# MusselGapeTracker_RevC.net
KiCad netlist of a schematic drawn in EAGLE
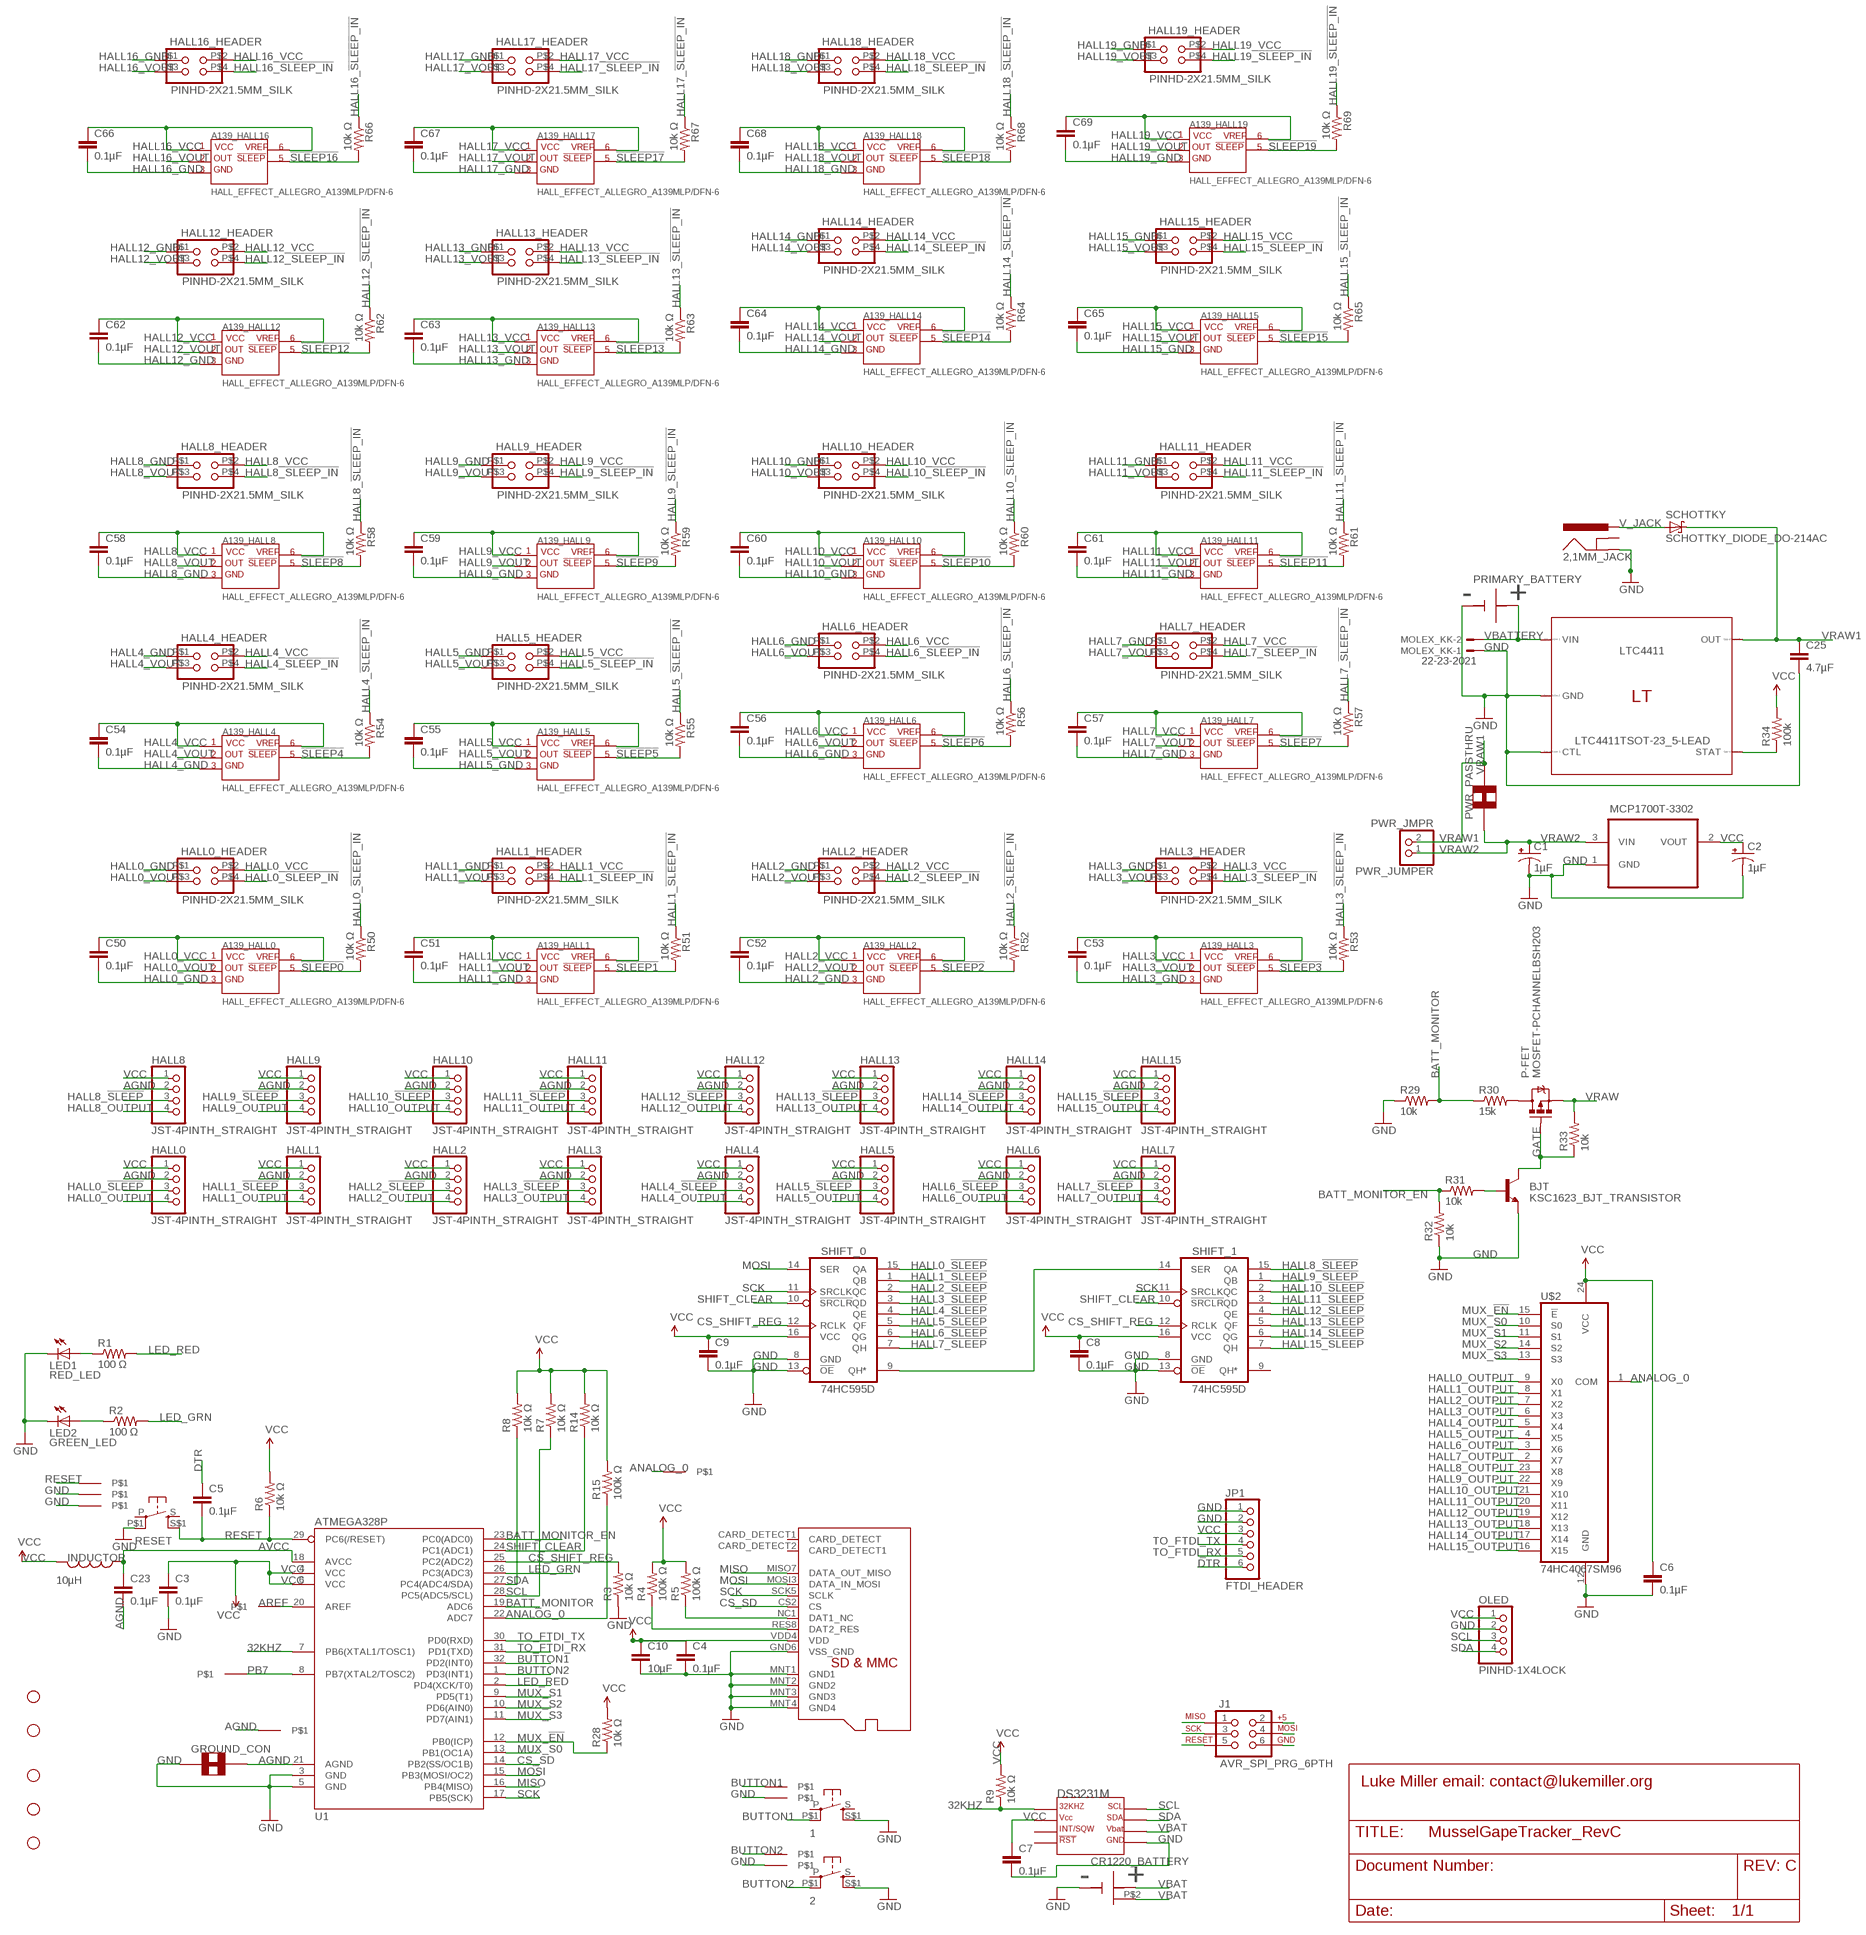
[diagram p0: schematic, sheet 1]

(export (version "E")
  (design (tool "Eeschema 10.0.6"))
  (components
    (comp (ref "1")
      (value "PUSHBUTTON_DPST_SMDSTANDARD")
      (footprint "eagle-import:PUSHBUTTON_DPST_SMD")
      (libsource (lib "eagle-import") (part "PUSHBUTTON_DPST_SMDSTANDARD"))
    )
    (comp (ref "2")
      (value "PUSHBUTTON_DPST_SMDSTANDARD")
      (footprint "eagle-import:PUSHBUTTON_DPST_SMD")
      (libsource (lib "eagle-import") (part "PUSHBUTTON_DPST_SMDSTANDARD"))
    )
    (comp (ref "2,1MM_JACK")
      (value "POWER_JACK_2,1MM")
      (footprint "eagle-import:POWER_JACK_DC_2,1MM")
      (libsource (lib "eagle-import") (part "POWER_JACK_2,1MM"))
    )
    (comp (ref "A139_HALL0")
      (value "HALL_EFFECT_ALLEGRO_A139MLP/DFN-6")
      (footprint "eagle-import:A139__HALL_EFFECT")
      (libsource (lib "eagle-import") (part "HALL_EFFECT_ALLEGRO_A139MLP/DFN-6"))
    )
    (comp (ref "A139_HALL1")
      (value "HALL_EFFECT_ALLEGRO_A139MLP/DFN-6")
      (footprint "eagle-import:A139__HALL_EFFECT")
      (libsource (lib "eagle-import") (part "HALL_EFFECT_ALLEGRO_A139MLP/DFN-6"))
    )
    (comp (ref "A139_HALL2")
      (value "HALL_EFFECT_ALLEGRO_A139MLP/DFN-6")
      (footprint "eagle-import:A139__HALL_EFFECT")
      (libsource (lib "eagle-import") (part "HALL_EFFECT_ALLEGRO_A139MLP/DFN-6"))
    )
    (comp (ref "A139_HALL3")
      (value "HALL_EFFECT_ALLEGRO_A139MLP/DFN-6")
      (footprint "eagle-import:A139__HALL_EFFECT")
      (libsource (lib "eagle-import") (part "HALL_EFFECT_ALLEGRO_A139MLP/DFN-6"))
    )
    (comp (ref "A139_HALL4")
      (value "HALL_EFFECT_ALLEGRO_A139MLP/DFN-6")
      (footprint "eagle-import:A139__HALL_EFFECT")
      (libsource (lib "eagle-import") (part "HALL_EFFECT_ALLEGRO_A139MLP/DFN-6"))
    )
    (comp (ref "A139_HALL5")
      (value "HALL_EFFECT_ALLEGRO_A139MLP/DFN-6")
      (footprint "eagle-import:A139__HALL_EFFECT")
      (libsource (lib "eagle-import") (part "HALL_EFFECT_ALLEGRO_A139MLP/DFN-6"))
    )
    (comp (ref "A139_HALL6")
      (value "HALL_EFFECT_ALLEGRO_A139MLP/DFN-6")
      (footprint "eagle-import:A139__HALL_EFFECT")
      (libsource (lib "eagle-import") (part "HALL_EFFECT_ALLEGRO_A139MLP/DFN-6"))
    )
    (comp (ref "A139_HALL7")
      (value "HALL_EFFECT_ALLEGRO_A139MLP/DFN-6")
      (footprint "eagle-import:A139__HALL_EFFECT")
      (libsource (lib "eagle-import") (part "HALL_EFFECT_ALLEGRO_A139MLP/DFN-6"))
    )
    (comp (ref "A139_HALL8")
      (value "HALL_EFFECT_ALLEGRO_A139MLP/DFN-6")
      (footprint "eagle-import:A139__HALL_EFFECT")
      (libsource (lib "eagle-import") (part "HALL_EFFECT_ALLEGRO_A139MLP/DFN-6"))
    )
    (comp (ref "A139_HALL9")
      (value "HALL_EFFECT_ALLEGRO_A139MLP/DFN-6")
      (footprint "eagle-import:A139__HALL_EFFECT")
      (libsource (lib "eagle-import") (part "HALL_EFFECT_ALLEGRO_A139MLP/DFN-6"))
    )
    (comp (ref "A139_HALL10")
      (value "HALL_EFFECT_ALLEGRO_A139MLP/DFN-6")
      (footprint "eagle-import:A139__HALL_EFFECT")
      (libsource (lib "eagle-import") (part "HALL_EFFECT_ALLEGRO_A139MLP/DFN-6"))
    )
    (comp (ref "A139_HALL11")
      (value "HALL_EFFECT_ALLEGRO_A139MLP/DFN-6")
      (footprint "eagle-import:A139__HALL_EFFECT")
      (libsource (lib "eagle-import") (part "HALL_EFFECT_ALLEGRO_A139MLP/DFN-6"))
    )
    (comp (ref "A139_HALL12")
      (value "HALL_EFFECT_ALLEGRO_A139MLP/DFN-6")
      (footprint "eagle-import:A139__HALL_EFFECT")
      (libsource (lib "eagle-import") (part "HALL_EFFECT_ALLEGRO_A139MLP/DFN-6"))
    )
    (comp (ref "A139_HALL13")
      (value "HALL_EFFECT_ALLEGRO_A139MLP/DFN-6")
      (footprint "eagle-import:A139__HALL_EFFECT")
      (libsource (lib "eagle-import") (part "HALL_EFFECT_ALLEGRO_A139MLP/DFN-6"))
    )
    (comp (ref "A139_HALL14")
      (value "HALL_EFFECT_ALLEGRO_A139MLP/DFN-6")
      (footprint "eagle-import:A139__HALL_EFFECT")
      (libsource (lib "eagle-import") (part "HALL_EFFECT_ALLEGRO_A139MLP/DFN-6"))
    )
    (comp (ref "A139_HALL15")
      (value "HALL_EFFECT_ALLEGRO_A139MLP/DFN-6")
      (footprint "eagle-import:A139__HALL_EFFECT")
      (libsource (lib "eagle-import") (part "HALL_EFFECT_ALLEGRO_A139MLP/DFN-6"))
    )
    (comp (ref "A139_HALL16")
      (value "HALL_EFFECT_ALLEGRO_A139MLP/DFN-6")
      (footprint "eagle-import:A139__HALL_EFFECT")
      (libsource (lib "eagle-import") (part "HALL_EFFECT_ALLEGRO_A139MLP/DFN-6"))
    )
    (comp (ref "A139_HALL17")
      (value "HALL_EFFECT_ALLEGRO_A139MLP/DFN-6")
      (footprint "eagle-import:A139__HALL_EFFECT")
      (libsource (lib "eagle-import") (part "HALL_EFFECT_ALLEGRO_A139MLP/DFN-6"))
    )
    (comp (ref "A139_HALL18")
      (value "HALL_EFFECT_ALLEGRO_A139MLP/DFN-6")
      (footprint "eagle-import:A139__HALL_EFFECT")
      (libsource (lib "eagle-import") (part "HALL_EFFECT_ALLEGRO_A139MLP/DFN-6"))
    )
    (comp (ref "A139_HALL19")
      (value "HALL_EFFECT_ALLEGRO_A139MLP/DFN-6")
      (footprint "eagle-import:A139__HALL_EFFECT")
      (libsource (lib "eagle-import") (part "HALL_EFFECT_ALLEGRO_A139MLP/DFN-6"))
    )
    (comp (ref "BJT")
      (value "KSC1623_BJT_TRANSISTOR")
      (footprint "eagle-import:SOT23")
      (libsource (lib "eagle-import") (part "KSC1623_BJT_TRANSISTOR"))
    )
    (comp (ref "C1")
      (value "1µF")
      (footprint "eagle-import:PANASONIC_B")
      (libsource (lib "eagle-import") (part "CPOL-USB"))
    )
    (comp (ref "C2")
      (value "1µF")
      (footprint "eagle-import:PANASONIC_B")
      (libsource (lib "eagle-import") (part "CPOL-USB"))
    )
    (comp (ref "C3")
      (value "0.1µF")
      (footprint "eagle-import:0603")
      (libsource (lib "eagle-import") (part "CAP0603"))
    )
    (comp (ref "C4")
      (value "0.1µF")
      (footprint "eagle-import:0603")
      (libsource (lib "eagle-import") (part "CAP0603"))
    )
    (comp (ref "C5")
      (value "0.1µF")
      (footprint "eagle-import:0603")
      (libsource (lib "eagle-import") (part "CAP0603"))
    )
    (comp (ref "C6")
      (value "0.1µF")
      (footprint "eagle-import:0603")
      (libsource (lib "eagle-import") (part "CAP0603"))
    )
    (comp (ref "C7")
      (value "0.1µF")
      (footprint "eagle-import:0603")
      (libsource (lib "eagle-import") (part "CAP0603"))
    )
    (comp (ref "C8")
      (value "0.1µF")
      (footprint "eagle-import:0603")
      (libsource (lib "eagle-import") (part "CAP0603"))
    )
    (comp (ref "C9")
      (value "0.1µF")
      (footprint "eagle-import:0603")
      (libsource (lib "eagle-import") (part "CAP0603"))
    )
    (comp (ref "C10")
      (value "10µF")
      (footprint "eagle-import:0603")
      (libsource (lib "eagle-import") (part "CAP0603"))
    )
    (comp (ref "C23")
      (value "0.1µF")
      (footprint "eagle-import:0603")
      (libsource (lib "eagle-import") (part "CAP0603"))
    )
    (comp (ref "C25")
      (value "4.7µF")
      (footprint "eagle-import:0603")
      (libsource (lib "eagle-import") (part "CAP0603"))
    )
    (comp (ref "C50")
      (value "0.1µF")
      (footprint "eagle-import:0603")
      (libsource (lib "eagle-import") (part "CAP0603"))
    )
    (comp (ref "C51")
      (value "0.1µF")
      (footprint "eagle-import:0603")
      (libsource (lib "eagle-import") (part "CAP0603"))
    )
    (comp (ref "C52")
      (value "0.1µF")
      (footprint "eagle-import:0603")
      (libsource (lib "eagle-import") (part "CAP0603"))
    )
    (comp (ref "C53")
      (value "0.1µF")
      (footprint "eagle-import:0603")
      (libsource (lib "eagle-import") (part "CAP0603"))
    )
    (comp (ref "C54")
      (value "0.1µF")
      (footprint "eagle-import:0603")
      (libsource (lib "eagle-import") (part "CAP0603"))
    )
    (comp (ref "C55")
      (value "0.1µF")
      (footprint "eagle-import:0603")
      (libsource (lib "eagle-import") (part "CAP0603"))
    )
    (comp (ref "C56")
      (value "0.1µF")
      (footprint "eagle-import:0603")
      (libsource (lib "eagle-import") (part "CAP0603"))
    )
    (comp (ref "C57")
      (value "0.1µF")
      (footprint "eagle-import:0603")
      (libsource (lib "eagle-import") (part "CAP0603"))
    )
    (comp (ref "C58")
      (value "0.1µF")
      (footprint "eagle-import:0603")
      (libsource (lib "eagle-import") (part "CAP0603"))
    )
    (comp (ref "C59")
      (value "0.1µF")
      (footprint "eagle-import:0603")
      (libsource (lib "eagle-import") (part "CAP0603"))
    )
    (comp (ref "C60")
      (value "0.1µF")
      (footprint "eagle-import:0603")
      (libsource (lib "eagle-import") (part "CAP0603"))
    )
    (comp (ref "C61")
      (value "0.1µF")
      (footprint "eagle-import:0603")
      (libsource (lib "eagle-import") (part "CAP0603"))
    )
    (comp (ref "C62")
      (value "0.1µF")
      (footprint "eagle-import:0603")
      (libsource (lib "eagle-import") (part "CAP0603"))
    )
    (comp (ref "C63")
      (value "0.1µF")
      (footprint "eagle-import:0603")
      (libsource (lib "eagle-import") (part "CAP0603"))
    )
    (comp (ref "C64")
      (value "0.1µF")
      (footprint "eagle-import:0603")
      (libsource (lib "eagle-import") (part "CAP0603"))
    )
    (comp (ref "C65")
      (value "0.1µF")
      (footprint "eagle-import:0603")
      (libsource (lib "eagle-import") (part "CAP0603"))
    )
    (comp (ref "C66")
      (value "0.1µF")
      (footprint "eagle-import:0603")
      (libsource (lib "eagle-import") (part "CAP0603"))
    )
    (comp (ref "C67")
      (value "0.1µF")
      (footprint "eagle-import:0603")
      (libsource (lib "eagle-import") (part "CAP0603"))
    )
    (comp (ref "C68")
      (value "0.1µF")
      (footprint "eagle-import:0603")
      (libsource (lib "eagle-import") (part "CAP0603"))
    )
    (comp (ref "C69")
      (value "0.1µF")
      (footprint "eagle-import:0603")
      (libsource (lib "eagle-import") (part "CAP0603"))
    )
    (comp (ref "CR1220_BATTERY")
      (value "CR1220_BATTERY_HOLDERSMD")
      (footprint "eagle-import:CR1220_BATTERY_HOLDER_SMD")
      (libsource (lib "eagle-import") (part "CR1220_BATTERY_HOLDERSMD"))
    )
    (comp (ref "DS3231M")
      (value "DS3231MSOIC-8")
      (footprint "eagle-import:DS3231M_SOIC8")
      (libsource (lib "eagle-import") (part "DS3231MSOIC-8"))
    )
    (comp (ref "GND")
      (value "PINHD-1X1SMALL")
      (footprint "eagle-import:1X01_SMALL")
      (libsource (lib "eagle-import") (part "PINHD-1X1SMALL"))
    )
    (comp (ref "GROUND_CON")
      (value "SOLDER_JUMPER_TRACESTANDARD")
      (footprint "eagle-import:SJ_2S-TRACE")
      (libsource (lib "eagle-import") (part "SOLDER_JUMPER_TRACESTANDARD"))
    )
    (comp (ref "HALL0")
      (value "JST-4PINTH_STRAIGHT")
      (footprint "eagle-import:JST-PH-4-THM")
      (libsource (lib "eagle-import") (part "JST-4PINTH_STRAIGHT"))
    )
    (comp (ref "HALL0_HEADER")
      (value "PINHD-2X21.5MM_SILK")
      (footprint "eagle-import:2X2_1.5MM")
      (libsource (lib "eagle-import") (part "PINHD-2X21.5MM_SILK"))
    )
    (comp (ref "HALL1")
      (value "JST-4PINTH_STRAIGHT")
      (footprint "eagle-import:JST-PH-4-THM")
      (libsource (lib "eagle-import") (part "JST-4PINTH_STRAIGHT"))
    )
    (comp (ref "HALL1_HEADER")
      (value "PINHD-2X21.5MM_SILK")
      (footprint "eagle-import:2X2_1.5MM")
      (libsource (lib "eagle-import") (part "PINHD-2X21.5MM_SILK"))
    )
    (comp (ref "HALL2")
      (value "JST-4PINTH_STRAIGHT")
      (footprint "eagle-import:JST-PH-4-THM")
      (libsource (lib "eagle-import") (part "JST-4PINTH_STRAIGHT"))
    )
    (comp (ref "HALL2_HEADER")
      (value "PINHD-2X21.5MM_SILK")
      (footprint "eagle-import:2X2_1.5MM")
      (libsource (lib "eagle-import") (part "PINHD-2X21.5MM_SILK"))
    )
    (comp (ref "HALL3")
      (value "JST-4PINTH_STRAIGHT")
      (footprint "eagle-import:JST-PH-4-THM")
      (libsource (lib "eagle-import") (part "JST-4PINTH_STRAIGHT"))
    )
    (comp (ref "HALL3_HEADER")
      (value "PINHD-2X21.5MM_SILK")
      (footprint "eagle-import:2X2_1.5MM")
      (libsource (lib "eagle-import") (part "PINHD-2X21.5MM_SILK"))
    )
    (comp (ref "HALL4")
      (value "JST-4PINTH_STRAIGHT")
      (footprint "eagle-import:JST-PH-4-THM")
      (libsource (lib "eagle-import") (part "JST-4PINTH_STRAIGHT"))
    )
    (comp (ref "HALL4_HEADER")
      (value "PINHD-2X21.5MM_SILK")
      (footprint "eagle-import:2X2_1.5MM")
      (libsource (lib "eagle-import") (part "PINHD-2X21.5MM_SILK"))
    )
    (comp (ref "HALL5")
      (value "JST-4PINTH_STRAIGHT")
      (footprint "eagle-import:JST-PH-4-THM")
      (libsource (lib "eagle-import") (part "JST-4PINTH_STRAIGHT"))
    )
    (comp (ref "HALL5_HEADER")
      (value "PINHD-2X21.5MM_SILK")
      (footprint "eagle-import:2X2_1.5MM")
      (libsource (lib "eagle-import") (part "PINHD-2X21.5MM_SILK"))
    )
    (comp (ref "HALL6")
      (value "JST-4PINTH_STRAIGHT")
      (footprint "eagle-import:JST-PH-4-THM")
      (libsource (lib "eagle-import") (part "JST-4PINTH_STRAIGHT"))
    )
    (comp (ref "HALL6_HEADER")
      (value "PINHD-2X21.5MM_SILK")
      (footprint "eagle-import:2X2_1.5MM")
      (libsource (lib "eagle-import") (part "PINHD-2X21.5MM_SILK"))
    )
    (comp (ref "HALL7")
      (value "JST-4PINTH_STRAIGHT")
      (footprint "eagle-import:JST-PH-4-THM")
      (libsource (lib "eagle-import") (part "JST-4PINTH_STRAIGHT"))
    )
    (comp (ref "HALL7_HEADER")
      (value "PINHD-2X21.5MM_SILK")
      (footprint "eagle-import:2X2_1.5MM")
      (libsource (lib "eagle-import") (part "PINHD-2X21.5MM_SILK"))
    )
    (comp (ref "HALL8")
      (value "JST-4PINTH_STRAIGHT")
      (footprint "eagle-import:JST-PH-4-THM")
      (libsource (lib "eagle-import") (part "JST-4PINTH_STRAIGHT"))
    )
    (comp (ref "HALL8_HEADER")
      (value "PINHD-2X21.5MM_SILK")
      (footprint "eagle-import:2X2_1.5MM")
      (libsource (lib "eagle-import") (part "PINHD-2X21.5MM_SILK"))
    )
    (comp (ref "HALL9")
      (value "JST-4PINTH_STRAIGHT")
      (footprint "eagle-import:JST-PH-4-THM")
      (libsource (lib "eagle-import") (part "JST-4PINTH_STRAIGHT"))
    )
    (comp (ref "HALL9_HEADER")
      (value "PINHD-2X21.5MM_SILK")
      (footprint "eagle-import:2X2_1.5MM")
      (libsource (lib "eagle-import") (part "PINHD-2X21.5MM_SILK"))
    )
    (comp (ref "HALL10")
      (value "JST-4PINTH_STRAIGHT")
      (footprint "eagle-import:JST-PH-4-THM")
      (libsource (lib "eagle-import") (part "JST-4PINTH_STRAIGHT"))
    )
    (comp (ref "HALL10_HEADER")
      (value "PINHD-2X21.5MM_SILK")
      (footprint "eagle-import:2X2_1.5MM")
      (libsource (lib "eagle-import") (part "PINHD-2X21.5MM_SILK"))
    )
    (comp (ref "HALL11")
      (value "JST-4PINTH_STRAIGHT")
      (footprint "eagle-import:JST-PH-4-THM")
      (libsource (lib "eagle-import") (part "JST-4PINTH_STRAIGHT"))
    )
    (comp (ref "HALL11_HEADER")
      (value "PINHD-2X21.5MM_SILK")
      (footprint "eagle-import:2X2_1.5MM")
      (libsource (lib "eagle-import") (part "PINHD-2X21.5MM_SILK"))
    )
    (comp (ref "HALL12")
      (value "JST-4PINTH_STRAIGHT")
      (footprint "eagle-import:JST-PH-4-THM")
      (libsource (lib "eagle-import") (part "JST-4PINTH_STRAIGHT"))
    )
    (comp (ref "HALL12_HEADER")
      (value "PINHD-2X21.5MM_SILK")
      (footprint "eagle-import:2X2_1.5MM")
      (libsource (lib "eagle-import") (part "PINHD-2X21.5MM_SILK"))
    )
    (comp (ref "HALL13")
      (value "JST-4PINTH_STRAIGHT")
      (footprint "eagle-import:JST-PH-4-THM")
      (libsource (lib "eagle-import") (part "JST-4PINTH_STRAIGHT"))
    )
    (comp (ref "HALL13_HEADER")
      (value "PINHD-2X21.5MM_SILK")
      (footprint "eagle-import:2X2_1.5MM")
      (libsource (lib "eagle-import") (part "PINHD-2X21.5MM_SILK"))
    )
    (comp (ref "HALL14")
      (value "JST-4PINTH_STRAIGHT")
      (footprint "eagle-import:JST-PH-4-THM")
      (libsource (lib "eagle-import") (part "JST-4PINTH_STRAIGHT"))
    )
    (comp (ref "HALL14_HEADER")
      (value "PINHD-2X21.5MM_SILK")
      (footprint "eagle-import:2X2_1.5MM")
      (libsource (lib "eagle-import") (part "PINHD-2X21.5MM_SILK"))
    )
    (comp (ref "HALL15")
      (value "JST-4PINTH_STRAIGHT")
      (footprint "eagle-import:JST-PH-4-THM")
      (libsource (lib "eagle-import") (part "JST-4PINTH_STRAIGHT"))
    )
    (comp (ref "HALL15_HEADER")
      (value "PINHD-2X21.5MM_SILK")
      (footprint "eagle-import:2X2_1.5MM")
      (libsource (lib "eagle-import") (part "PINHD-2X21.5MM_SILK"))
    )
    (comp (ref "HALL16_HEADER")
      (value "PINHD-2X21.5MM_SILK")
      (footprint "eagle-import:2X2_1.5MM")
      (libsource (lib "eagle-import") (part "PINHD-2X21.5MM_SILK"))
    )
    (comp (ref "HALL17_HEADER")
      (value "PINHD-2X21.5MM_SILK")
      (footprint "eagle-import:2X2_1.5MM")
      (libsource (lib "eagle-import") (part "PINHD-2X21.5MM_SILK"))
    )
    (comp (ref "HALL18_HEADER")
      (value "PINHD-2X21.5MM_SILK")
      (footprint "eagle-import:2X2_1.5MM")
      (libsource (lib "eagle-import") (part "PINHD-2X21.5MM_SILK"))
    )
    (comp (ref "HALL19_HEADER")
      (value "PINHD-2X21.5MM_SILK")
      (footprint "eagle-import:2X2_1.5MM")
      (libsource (lib "eagle-import") (part "PINHD-2X21.5MM_SILK"))
    )
    (comp (ref "INDUCTOR")
      (value "10µH")
      (footprint "eagle-import:I_0805")
      (libsource (lib "eagle-import") (part "INDUCTOR0805_TY"))
    )
    (comp (ref "J1")
      (value "AVR_SPI_PRG_6PTH")
      (footprint "eagle-import:2X3")
      (libsource (lib "eagle-import") (part "AVR_SPI_PRG_6PTH"))
    )
    (comp (ref "JP1")
      (value "FTDI_HEADER")
      (footprint "eagle-import:1X06-RIGHT_ANGLE")
      (libsource (lib "eagle-import") (part "PINHD-1X6RA"))
    )
    (comp (ref "LED1")
      (value "RED_LED")
      (footprint "eagle-import:CHIPLED_0805")
      (libsource (lib "eagle-import") (part "LED0805"))
    )
    (comp (ref "LED2")
      (value "GREEN_LED")
      (footprint "eagle-import:CHIPLED_0805")
      (libsource (lib "eagle-import") (part "LED0805"))
    )
    (comp (ref "LTC4411")
      (value "LTC4411TSOT-23_5-LEAD")
      (footprint "eagle-import:TSOT-23_5-LEAD")
      (libsource (lib "eagle-import") (part "LTC4411TSOT-23_5-LEAD"))
    )
    (comp (ref "MCP1700T-3302")
      (value "MCP1700T-3302E/TT")
      (footprint "eagle-import:SOT95P237X112-3N")
      (libsource (lib "eagle-import") (part "MCP1700T-3302E/TT"))
    )
    (comp (ref "MOLEX_KK")
      (value "22-23-2021")
      (footprint "eagle-import:22-23-2021")
      (fields (field (name "MF") "MOLEX"))
      (libsource (lib "eagle-import") (part "22-23-2021"))
    )
    (comp (ref "OLED")
      (value "PINHD-1X4LOCK")
      (footprint "eagle-import:1X04_LOCK")
      (libsource (lib "eagle-import") (part "PINHD-1X4LOCK"))
    )
    (comp (ref "P-FET")
      (value "MOSFET-PCHANNELBSH203")
      (footprint "eagle-import:SOT23-3")
      (libsource (lib "eagle-import") (part "MOSFET-PCHANNELBSH203"))
    )
    (comp (ref "PB7")
      (value "PINHD-1X1SMALL")
      (footprint "eagle-import:1X01_SMALL")
      (libsource (lib "eagle-import") (part "PINHD-1X1SMALL"))
    )
    (comp (ref "PRIMARY_BATTERY")
      (value "BATTERY_4XAA")
      (footprint "eagle-import:BATTERY_4XAA_PTH")
      (libsource (lib "eagle-import") (part "BATTERY_4XAA"))
    )
    (comp (ref "PWR_JUMPER")
      (value "PWR_JMPR")
      (footprint "eagle-import:1X02_NOSILK")
      (libsource (lib "eagle-import") (part "PINHD-1X2NOSILK"))
    )
    (comp (ref "PWR_PASSTHRU")
      (value "PWR")
      (footprint "eagle-import:SJ_2S-TRACE")
      (libsource (lib "eagle-import") (part "SOLDER_JUMPER_TRACESTANDARD"))
    )
    (comp (ref "R1")
      (value "100 Ω")
      (footprint "eagle-import:R0603")
      (libsource (lib "eagle-import") (part "RESISTOR_SMDR0603"))
    )
    (comp (ref "R2")
      (value "100 Ω")
      (footprint "eagle-import:R0603")
      (libsource (lib "eagle-import") (part "RESISTOR_SMDR0603"))
    )
    (comp (ref "R3")
      (value "10k Ω")
      (footprint "eagle-import:R0603")
      (libsource (lib "eagle-import") (part "RESISTOR_SMDR0603"))
    )
    (comp (ref "R4")
      (value "100k Ω")
      (footprint "eagle-import:R0603")
      (libsource (lib "eagle-import") (part "RESISTOR_SMDR0603"))
    )
    (comp (ref "R5")
      (value "100k Ω")
      (footprint "eagle-import:R0603")
      (libsource (lib "eagle-import") (part "RESISTOR_SMDR0603"))
    )
    (comp (ref "R6")
      (value "10k Ω")
      (footprint "eagle-import:R0603")
      (libsource (lib "eagle-import") (part "RESISTOR_SMDR0603"))
    )
    (comp (ref "R7")
      (value "10k Ω")
      (footprint "eagle-import:R0603")
      (libsource (lib "eagle-import") (part "RESISTOR_SMDR0603"))
    )
    (comp (ref "R8")
      (value "10k Ω")
      (footprint "eagle-import:R0603")
      (libsource (lib "eagle-import") (part "RESISTOR_SMDR0603"))
    )
    (comp (ref "R9")
      (value "10k Ω")
      (footprint "eagle-import:R0603")
      (libsource (lib "eagle-import") (part "RESISTOR_SMDR0603"))
    )
    (comp (ref "R14")
      (value "10k Ω")
      (footprint "eagle-import:R0603")
      (libsource (lib "eagle-import") (part "RESISTOR_SMDR0603"))
    )
    (comp (ref "R15")
      (value "100k Ω")
      (footprint "eagle-import:R0603")
      (libsource (lib "eagle-import") (part "RESISTOR_SMDR0603"))
    )
    (comp (ref "R28")
      (value "10k Ω")
      (footprint "eagle-import:R0603")
      (libsource (lib "eagle-import") (part "RESISTOR_SMDR0603"))
    )
    (comp (ref "R29")
      (value "10k")
      (footprint "eagle-import:R0603")
      (libsource (lib "eagle-import") (part "RESISTOR_SMDR0603"))
    )
    (comp (ref "R30")
      (value "15k")
      (footprint "eagle-import:R0603")
      (libsource (lib "eagle-import") (part "RESISTOR_SMDR0603"))
    )
    (comp (ref "R31")
      (value "10k")
      (footprint "eagle-import:R0603")
      (libsource (lib "eagle-import") (part "RESISTOR_SMDR0603"))
    )
    (comp (ref "R32")
      (value "10k")
      (footprint "eagle-import:R0603")
      (libsource (lib "eagle-import") (part "RESISTOR_SMDR0603"))
    )
    (comp (ref "R33")
      (value "10k")
      (footprint "eagle-import:R0603")
      (libsource (lib "eagle-import") (part "RESISTOR_SMDR0603"))
    )
    (comp (ref "R34")
      (value "100k")
      (footprint "eagle-import:R0603")
      (libsource (lib "eagle-import") (part "RESISTOR_SMDR0603"))
    )
    (comp (ref "R50")
      (value "10k Ω")
      (footprint "eagle-import:R0603")
      (libsource (lib "eagle-import") (part "RESISTOR_SMDR0603"))
    )
    (comp (ref "R51")
      (value "10k Ω")
      (footprint "eagle-import:R0603")
      (libsource (lib "eagle-import") (part "RESISTOR_SMDR0603"))
    )
    (comp (ref "R52")
      (value "10k Ω")
      (footprint "eagle-import:R0603")
      (libsource (lib "eagle-import") (part "RESISTOR_SMDR0603"))
    )
    (comp (ref "R53")
      (value "10k Ω")
      (footprint "eagle-import:R0603")
      (libsource (lib "eagle-import") (part "RESISTOR_SMDR0603"))
    )
    (comp (ref "R54")
      (value "10k Ω")
      (footprint "eagle-import:R0603")
      (libsource (lib "eagle-import") (part "RESISTOR_SMDR0603"))
    )
    (comp (ref "R55")
      (value "10k Ω")
      (footprint "eagle-import:R0603")
      (libsource (lib "eagle-import") (part "RESISTOR_SMDR0603"))
    )
    (comp (ref "R56")
      (value "10k Ω")
      (footprint "eagle-import:R0603")
      (libsource (lib "eagle-import") (part "RESISTOR_SMDR0603"))
    )
    (comp (ref "R57")
      (value "10k Ω")
      (footprint "eagle-import:R0603")
      (libsource (lib "eagle-import") (part "RESISTOR_SMDR0603"))
    )
    (comp (ref "R58")
      (value "10k Ω")
      (footprint "eagle-import:R0603")
      (libsource (lib "eagle-import") (part "RESISTOR_SMDR0603"))
    )
    (comp (ref "R59")
      (value "10k Ω")
      (footprint "eagle-import:R0603")
      (libsource (lib "eagle-import") (part "RESISTOR_SMDR0603"))
    )
    (comp (ref "R60")
      (value "10k Ω")
      (footprint "eagle-import:R0603")
      (libsource (lib "eagle-import") (part "RESISTOR_SMDR0603"))
    )
    (comp (ref "R61")
      (value "10k Ω")
      (footprint "eagle-import:R0603")
      (libsource (lib "eagle-import") (part "RESISTOR_SMDR0603"))
    )
    (comp (ref "R62")
      (value "10k Ω")
      (footprint "eagle-import:R0603")
      (libsource (lib "eagle-import") (part "RESISTOR_SMDR0603"))
    )
    (comp (ref "R63")
      (value "10k Ω")
      (footprint "eagle-import:R0603")
      (libsource (lib "eagle-import") (part "RESISTOR_SMDR0603"))
    )
    (comp (ref "R64")
      (value "10k Ω")
      (footprint "eagle-import:R0603")
      (libsource (lib "eagle-import") (part "RESISTOR_SMDR0603"))
    )
    (comp (ref "R65")
      (value "10k Ω")
      (footprint "eagle-import:R0603")
      (libsource (lib "eagle-import") (part "RESISTOR_SMDR0603"))
    )
    (comp (ref "R66")
      (value "10k Ω")
      (footprint "eagle-import:R0603")
      (libsource (lib "eagle-import") (part "RESISTOR_SMDR0603"))
    )
    (comp (ref "R67")
      (value "10k Ω")
      (footprint "eagle-import:R0603")
      (libsource (lib "eagle-import") (part "RESISTOR_SMDR0603"))
    )
    (comp (ref "R68")
      (value "10k Ω")
      (footprint "eagle-import:R0603")
      (libsource (lib "eagle-import") (part "RESISTOR_SMDR0603"))
    )
    (comp (ref "R69")
      (value "10k Ω")
      (footprint "eagle-import:R0603")
      (libsource (lib "eagle-import") (part "RESISTOR_SMDR0603"))
    )
    (comp (ref "RESET")
      (value "PUSHBUTTON_DPST_SMDSTANDARD")
      (footprint "eagle-import:PUSHBUTTON_DPST_SMD")
      (libsource (lib "eagle-import") (part "PUSHBUTTON_DPST_SMDSTANDARD"))
    )
    (comp (ref "SCHOTTKY")
      (value "SCHOTTKY_DIODE_DO-214AC")
      (footprint "eagle-import:DO214AC")
      (libsource (lib "eagle-import") (part "SCHOTTKY_DIODE_DO-214AC"))
    )
    (comp (ref "SHIFT_0")
      (value "74HC595D")
      (footprint "eagle-import:SO16")
      (libsource (lib "eagle-import") (part "74HC595D"))
    )
    (comp (ref "SHIFT_1")
      (value "74HC595D")
      (footprint "eagle-import:SO16")
      (libsource (lib "eagle-import") (part "74HC595D"))
    )
    (comp (ref "STANDOFF1")
      (value "STAND-OFF4-40")
      (footprint "eagle-import:STAND-OFF")
      (libsource (lib "eagle-import") (part "STAND-OFF4-40"))
    )
    (comp (ref "STANDOFF2")
      (value "STAND-OFF4-40")
      (footprint "eagle-import:STAND-OFF")
      (libsource (lib "eagle-import") (part "STAND-OFF4-40"))
    )
    (comp (ref "STANDOFF3")
      (value "STAND-OFF4-40")
      (footprint "eagle-import:STAND-OFF")
      (libsource (lib "eagle-import") (part "STAND-OFF4-40"))
    )
    (comp (ref "STANDOFF4_M2")
      (value "STAND-OFFM2")
      (footprint "eagle-import:STAND-OFF_M2")
      (libsource (lib "eagle-import") (part "STAND-OFFM2"))
    )
    (comp (ref "STANDOFF5_M2")
      (value "STAND-OFFM2")
      (footprint "eagle-import:STAND-OFF_M2")
      (libsource (lib "eagle-import") (part "STAND-OFFM2"))
    )
    (comp (ref "U$1")
      (value "MICROSD_MOLEX_REVERSECURRENT")
      (footprint "eagle-import:MICROSD_SOCKET_MOLEX_REVERSEMOUNT")
      (libsource (lib "eagle-import") (part "MICROSD_MOLEX_REVERSECURRENT"))
    )
    (comp (ref "U$2")
      (value "74HC4067SM96")
      (footprint "eagle-import:SSOP24")
      (libsource (lib "eagle-import") (part "74HC4067SM96"))
    )
    (comp (ref "U$3")
      (value "PINHD-1X1SMALL")
      (footprint "eagle-import:1X01_SMALL")
      (libsource (lib "eagle-import") (part "PINHD-1X1SMALL"))
    )
    (comp (ref "U$4")
      (value "PINHD-1X1SMALL")
      (footprint "eagle-import:1X01_SMALL")
      (libsource (lib "eagle-import") (part "PINHD-1X1SMALL"))
    )
    (comp (ref "U$6")
      (value "PINHD-1X1SMALL")
      (footprint "eagle-import:1X01_SMALL")
      (libsource (lib "eagle-import") (part "PINHD-1X1SMALL"))
    )
    (comp (ref "U$7")
      (value "PINHD-1X1SMALL")
      (footprint "eagle-import:1X01_SMALL")
      (libsource (lib "eagle-import") (part "PINHD-1X1SMALL"))
    )
    (comp (ref "U$8")
      (value "PINHD-1X1SMALL")
      (footprint "eagle-import:1X01_SMALL")
      (libsource (lib "eagle-import") (part "PINHD-1X1SMALL"))
    )
    (comp (ref "U$9")
      (value "PINHD-1X1SMALL")
      (footprint "eagle-import:1X01_SMALL")
      (libsource (lib "eagle-import") (part "PINHD-1X1SMALL"))
    )
    (comp (ref "U$10")
      (value "PINHD-1X1SMALL")
      (footprint "eagle-import:1X01_SMALL")
      (libsource (lib "eagle-import") (part "PINHD-1X1SMALL"))
    )
    (comp (ref "U$11")
      (value "PINHD-1X1SMALL")
      (footprint "eagle-import:1X01_SMALL")
      (libsource (lib "eagle-import") (part "PINHD-1X1SMALL"))
    )
    (comp (ref "U$17")
      (value "PINHD-1X1SMALL")
      (footprint "eagle-import:1X01_SMALL")
      (libsource (lib "eagle-import") (part "PINHD-1X1SMALL"))
    )
    (comp (ref "U1")
      (value "ATMEGA328P")
      (footprint "eagle-import:TQFP32-08")
      (libsource (lib "eagle-import") (part "ATMEGA328_SMT"))
    )
  )
  (nets
    (net (code "1") (name "/32KHZ") (class "Default")
      (node (ref "DS3231M") (pin "1") (pinfunction "P$1_32KHZ_1") (pintype "bidirectional"))
      (node (ref "R9") (pin "1") (pinfunction "1_1") (pintype "passive"))
      (node (ref "U1") (pin "7") (pinfunction "PB6(XTAL1/TOSC1)_7") (pintype "bidirectional"))
    )
    (net (code "2") (name "/AGND") (class "Default")
      (node (ref "C23") (pin "2") (pinfunction "2_2") (pintype "passive"))
      (node (ref "GROUND_CON") (pin "2") (pinfunction "P$2_2") (pintype "bidirectional"))
      (node (ref "HALL0") (pin "2") (pinfunction "2_2") (pintype "passive"))
      (node (ref "HALL1") (pin "2") (pinfunction "2_2") (pintype "passive"))
      (node (ref "HALL10") (pin "2") (pinfunction "2_2") (pintype "passive"))
      (node (ref "HALL11") (pin "2") (pinfunction "2_2") (pintype "passive"))
      (node (ref "HALL12") (pin "2") (pinfunction "2_2") (pintype "passive"))
      (node (ref "HALL13") (pin "2") (pinfunction "2_2") (pintype "passive"))
      (node (ref "HALL14") (pin "2") (pinfunction "2_2") (pintype "passive"))
      (node (ref "HALL15") (pin "2") (pinfunction "2_2") (pintype "passive"))
      (node (ref "HALL2") (pin "2") (pinfunction "2_2") (pintype "passive"))
      (node (ref "HALL3") (pin "2") (pinfunction "2_2") (pintype "passive"))
      (node (ref "HALL4") (pin "2") (pinfunction "2_2") (pintype "passive"))
      (node (ref "HALL5") (pin "2") (pinfunction "2_2") (pintype "passive"))
      (node (ref "HALL6") (pin "2") (pinfunction "2_2") (pintype "passive"))
      (node (ref "HALL7") (pin "2") (pinfunction "2_2") (pintype "passive"))
      (node (ref "HALL8") (pin "2") (pinfunction "2_2") (pintype "passive"))
      (node (ref "HALL9") (pin "2") (pinfunction "2_2") (pintype "passive"))
      (node (ref "U$11") (pin "1") (pinfunction "P$1_1") (pintype "bidirectional"))
      (node (ref "U1") (pin "21") (pinfunction "AGND_21") (pintype "bidirectional"))
    )
    (net (code "3") (name "/ANALOG_0") (class "Default")
      (node (ref "R15") (pin "1") (pinfunction "1_1") (pintype "passive"))
      (node (ref "U$10") (pin "1") (pinfunction "P$1_1") (pintype "bidirectional"))
      (node (ref "U$2") (pin "1") (pinfunction "COM_1") (pintype "output"))
      (node (ref "U1") (pin "22") (pinfunction "ADC7_22") (pintype "bidirectional"))
    )
    (net (code "4") (name "/AREF") (class "Default")
      (node (ref "U$17") (pin "1") (pinfunction "P$1_1") (pintype "bidirectional"))
      (node (ref "U1") (pin "20") (pinfunction "AREF_20") (pintype "bidirectional"))
    )
    (net (code "5") (name "/AVCC") (class "Default")
      (node (ref "C23") (pin "1") (pinfunction "1_1") (pintype "passive"))
      (node (ref "INDUCTOR") (pin "P$1") (pinfunction "1_P$1") (pintype "passive"))
      (node (ref "U1") (pin "18") (pinfunction "AVCC_18") (pintype "bidirectional"))
    )
    (net (code "6") (name "/BATT_MONITOR") (class "Default")
      (node (ref "R29") (pin "2") (pinfunction "2_2") (pintype "passive"))
      (node (ref "R30") (pin "1") (pinfunction "1_1") (pintype "passive"))
      (node (ref "U1") (pin "19") (pinfunction "ADC6_19") (pintype "bidirectional"))
    )
    (net (code "7") (name "/BATT_MONITOR_EN") (class "Default")
      (node (ref "R31") (pin "1") (pinfunction "1_1") (pintype "passive"))
      (node (ref "R32") (pin "2") (pinfunction "2_2") (pintype "passive"))
      (node (ref "U1") (pin "23") (pinfunction "PC0(ADC0)_23") (pintype "bidirectional"))
    )
    (net (code "8") (name "/BUTTON1") (class "Default")
      (node (ref "1") (pin "P$1") (pinfunction "P1_P$1") (pintype "passive"))
      (node (ref "U$6") (pin "1") (pinfunction "P$1_1") (pintype "bidirectional"))
      (node (ref "U1") (pin "32") (pinfunction "PD2(INT0)_32") (pintype "bidirectional"))
    )
    (net (code "9") (name "/BUTTON2") (class "Default")
      (node (ref "2") (pin "P$1") (pinfunction "P1_P$1") (pintype "passive"))
      (node (ref "U$8") (pin "1") (pinfunction "P$1_1") (pintype "bidirectional"))
      (node (ref "U1") (pin "1") (pinfunction "PD3(INT1)_1") (pintype "bidirectional"))
    )
    (net (code "10") (name "/CS_SD") (class "Default")
      (node (ref "U$1") (pin "CS2") (pinfunction "CS_CS2") (pintype "input"))
      (node (ref "U1") (pin "14") (pinfunction "PB2(SS/OC1B)_14") (pintype "bidirectional"))
    )
    (net (code "11") (name "/CS_SHIFT_REG") (class "Default")
      (node (ref "R3") (pin "2") (pinfunction "2_2") (pintype "passive"))
      (node (ref "SHIFT_0") (pin "12") (pinfunction "RCLK_12") (pintype "input"))
      (node (ref "SHIFT_1") (pin "12") (pinfunction "RCLK_12") (pintype "input"))
      (node (ref "U1") (pin "25") (pinfunction "PC2(ADC2)_25") (pintype "bidirectional"))
    )
    (net (code "12") (name "/DTR") (class "Default")
      (node (ref "C5") (pin "1") (pinfunction "1_1") (pintype "passive"))
      (node (ref "JP1") (pin "6") (pinfunction "6_6") (pintype "passive"))
    )
    (net (code "13") (name "/GATE") (class "Default")
      (node (ref "BJT") (pin "3") (pinfunction "C_3") (pintype "passive"))
      (node (ref "P-FET") (pin "1") (pinfunction "G_1") (pintype "passive"))
      (node (ref "R33") (pin "1") (pinfunction "1_1") (pintype "passive"))
    )
    (net (code "14") (name "/HALL0_GND") (class "Default")
      (node (ref "A139_HALL0") (pin "P$3_4") (pinfunction "P$3_P$3_4") (pintype "bidirectional"))
      (node (ref "C50") (pin "2") (pinfunction "2_2") (pintype "passive"))
      (node (ref "HALL0_HEADER") (pin "P$1") (pinfunction "1_P$1") (pintype "passive"))
    )
    (net (code "15") (name "/HALL0_OUTPUT") (class "Default")
      (node (ref "HALL0") (pin "4") (pinfunction "4_4") (pintype "passive"))
      (node (ref "U$2") (pin "9") (pinfunction "X0_9") (pintype "input"))
    )
    (net (code "16") (name "/HALL0_VCC") (class "Default")
      (node (ref "A139_HALL0") (pin "P$1") (pinfunction "P$1_P$1") (pintype "bidirectional"))
      (node (ref "A139_HALL0") (pin "P$6") (pinfunction "P$6_P$6") (pintype "bidirectional"))
      (node (ref "C50") (pin "1") (pinfunction "1_1") (pintype "passive"))
      (node (ref "HALL0_HEADER") (pin "P$2") (pinfunction "2_P$2") (pintype "passive"))
    )
    (net (code "17") (name "/HALL0_VOUT") (class "Default")
      (node (ref "A139_HALL0") (pin "P$2") (pinfunction "P$2_P$2") (pintype "bidirectional"))
      (node (ref "HALL0_HEADER") (pin "P$3") (pinfunction "3_P$3") (pintype "passive"))
    )
    (net (code "18") (name "/HALL0_~{SLEEP_IN}") (class "Default")
      (node (ref "HALL0_HEADER") (pin "P$4") (pinfunction "4_P$4") (pintype "passive"))
      (node (ref "R50") (pin "1") (pinfunction "1_1") (pintype "passive"))
    )
    (net (code "19") (name "/HALL0_~{SLEEP}") (class "Default")
      (node (ref "HALL0") (pin "3") (pinfunction "3_3") (pintype "passive"))
      (node (ref "SHIFT_0") (pin "15") (pinfunction "QA_15") (pintype "tri_state"))
    )
    (net (code "20") (name "/HALL1_GND") (class "Default")
      (node (ref "A139_HALL1") (pin "P$3_4") (pinfunction "P$3_P$3_4") (pintype "bidirectional"))
      (node (ref "C51") (pin "2") (pinfunction "2_2") (pintype "passive"))
      (node (ref "HALL1_HEADER") (pin "P$1") (pinfunction "1_P$1") (pintype "passive"))
    )
    (net (code "21") (name "/HALL1_OUTPUT") (class "Default")
      (node (ref "HALL1") (pin "4") (pinfunction "4_4") (pintype "passive"))
      (node (ref "U$2") (pin "8") (pinfunction "X1_8") (pintype "input"))
    )
    (net (code "22") (name "/HALL1_VCC") (class "Default")
      (node (ref "A139_HALL1") (pin "P$1") (pinfunction "P$1_P$1") (pintype "bidirectional"))
      (node (ref "A139_HALL1") (pin "P$6") (pinfunction "P$6_P$6") (pintype "bidirectional"))
      (node (ref "C51") (pin "1") (pinfunction "1_1") (pintype "passive"))
      (node (ref "HALL1_HEADER") (pin "P$2") (pinfunction "2_P$2") (pintype "passive"))
    )
    (net (code "23") (name "/HALL1_VOUT") (class "Default")
      (node (ref "A139_HALL1") (pin "P$2") (pinfunction "P$2_P$2") (pintype "bidirectional"))
      (node (ref "HALL1_HEADER") (pin "P$3") (pinfunction "3_P$3") (pintype "passive"))
    )
    (net (code "24") (name "/HALL1_~{SLEEP_IN}") (class "Default")
      (node (ref "HALL1_HEADER") (pin "P$4") (pinfunction "4_P$4") (pintype "passive"))
      (node (ref "R51") (pin "1") (pinfunction "1_1") (pintype "passive"))
    )
    (net (code "25") (name "/HALL1_~{SLEEP}") (class "Default")
      (node (ref "HALL1") (pin "3") (pinfunction "3_3") (pintype "passive"))
      (node (ref "SHIFT_0") (pin "1") (pinfunction "QB_1") (pintype "tri_state"))
    )
    (net (code "26") (name "/HALL2_GND") (class "Default")
      (node (ref "A139_HALL2") (pin "P$3_4") (pinfunction "P$3_P$3_4") (pintype "bidirectional"))
      (node (ref "C52") (pin "2") (pinfunction "2_2") (pintype "passive"))
      (node (ref "HALL2_HEADER") (pin "P$1") (pinfunction "1_P$1") (pintype "passive"))
    )
    (net (code "27") (name "/HALL2_OUTPUT") (class "Default")
      (node (ref "HALL2") (pin "4") (pinfunction "4_4") (pintype "passive"))
      (node (ref "U$2") (pin "7") (pinfunction "X2_7") (pintype "input"))
    )
    (net (code "28") (name "/HALL2_VCC") (class "Default")
      (node (ref "A139_HALL2") (pin "P$1") (pinfunction "P$1_P$1") (pintype "bidirectional"))
      (node (ref "A139_HALL2") (pin "P$6") (pinfunction "P$6_P$6") (pintype "bidirectional"))
      (node (ref "C52") (pin "1") (pinfunction "1_1") (pintype "passive"))
      (node (ref "HALL2_HEADER") (pin "P$2") (pinfunction "2_P$2") (pintype "passive"))
    )
    (net (code "29") (name "/HALL2_VOUT") (class "Default")
      (node (ref "A139_HALL2") (pin "P$2") (pinfunction "P$2_P$2") (pintype "bidirectional"))
      (node (ref "HALL2_HEADER") (pin "P$3") (pinfunction "3_P$3") (pintype "passive"))
    )
    (net (code "30") (name "/HALL2_~{SLEEP_IN}") (class "Default")
      (node (ref "HALL2_HEADER") (pin "P$4") (pinfunction "4_P$4") (pintype "passive"))
      (node (ref "R52") (pin "1") (pinfunction "1_1") (pintype "passive"))
    )
    (net (code "31") (name "/HALL2_~{SLEEP}") (class "Default")
      (node (ref "HALL2") (pin "3") (pinfunction "3_3") (pintype "passive"))
      (node (ref "SHIFT_0") (pin "2") (pinfunction "QC_2") (pintype "tri_state"))
    )
    (net (code "32") (name "/HALL3_GND") (class "Default")
      (node (ref "A139_HALL3") (pin "P$3_4") (pinfunction "P$3_P$3_4") (pintype "bidirectional"))
      (node (ref "C53") (pin "2") (pinfunction "2_2") (pintype "passive"))
      (node (ref "HALL3_HEADER") (pin "P$1") (pinfunction "1_P$1") (pintype "passive"))
    )
    (net (code "33") (name "/HALL3_OUTPUT") (class "Default")
      (node (ref "HALL3") (pin "4") (pinfunction "4_4") (pintype "passive"))
      (node (ref "U$2") (pin "6") (pinfunction "X3_6") (pintype "input"))
    )
    (net (code "34") (name "/HALL3_VCC") (class "Default")
      (node (ref "A139_HALL3") (pin "P$1") (pinfunction "P$1_P$1") (pintype "bidirectional"))
      (node (ref "A139_HALL3") (pin "P$6") (pinfunction "P$6_P$6") (pintype "bidirectional"))
      (node (ref "C53") (pin "1") (pinfunction "1_1") (pintype "passive"))
      (node (ref "HALL3_HEADER") (pin "P$2") (pinfunction "2_P$2") (pintype "passive"))
    )
    (net (code "35") (name "/HALL3_VOUT") (class "Default")
      (node (ref "A139_HALL3") (pin "P$2") (pinfunction "P$2_P$2") (pintype "bidirectional"))
      (node (ref "HALL3_HEADER") (pin "P$3") (pinfunction "3_P$3") (pintype "passive"))
    )
    (net (code "36") (name "/HALL3_~{SLEEP_IN}") (class "Default")
      (node (ref "HALL3_HEADER") (pin "P$4") (pinfunction "4_P$4") (pintype "passive"))
      (node (ref "R53") (pin "1") (pinfunction "1_1") (pintype "passive"))
    )
    (net (code "37") (name "/HALL3_~{SLEEP}") (class "Default")
      (node (ref "HALL3") (pin "3") (pinfunction "3_3") (pintype "passive"))
      (node (ref "SHIFT_0") (pin "3") (pinfunction "QD_3") (pintype "tri_state"))
    )
    (net (code "38") (name "/HALL4_GND") (class "Default")
      (node (ref "A139_HALL4") (pin "P$3_4") (pinfunction "P$3_P$3_4") (pintype "bidirectional"))
      (node (ref "C54") (pin "2") (pinfunction "2_2") (pintype "passive"))
      (node (ref "HALL4_HEADER") (pin "P$1") (pinfunction "1_P$1") (pintype "passive"))
    )
    (net (code "39") (name "/HALL4_OUTPUT") (class "Default")
      (node (ref "HALL4") (pin "4") (pinfunction "4_4") (pintype "passive"))
      (node (ref "U$2") (pin "5") (pinfunction "X4_5") (pintype "input"))
    )
    (net (code "40") (name "/HALL4_VCC") (class "Default")
      (node (ref "A139_HALL4") (pin "P$1") (pinfunction "P$1_P$1") (pintype "bidirectional"))
      (node (ref "A139_HALL4") (pin "P$6") (pinfunction "P$6_P$6") (pintype "bidirectional"))
      (node (ref "C54") (pin "1") (pinfunction "1_1") (pintype "passive"))
      (node (ref "HALL4_HEADER") (pin "P$2") (pinfunction "2_P$2") (pintype "passive"))
    )
    (net (code "41") (name "/HALL4_VOUT") (class "Default")
      (node (ref "A139_HALL4") (pin "P$2") (pinfunction "P$2_P$2") (pintype "bidirectional"))
      (node (ref "HALL4_HEADER") (pin "P$3") (pinfunction "3_P$3") (pintype "passive"))
    )
    (net (code "42") (name "/HALL4_~{SLEEP_IN}") (class "Default")
      (node (ref "HALL4_HEADER") (pin "P$4") (pinfunction "4_P$4") (pintype "passive"))
      (node (ref "R54") (pin "1") (pinfunction "1_1") (pintype "passive"))
    )
    (net (code "43") (name "/HALL4_~{SLEEP}") (class "Default")
      (node (ref "HALL4") (pin "3") (pinfunction "3_3") (pintype "passive"))
      (node (ref "SHIFT_0") (pin "4") (pinfunction "QE_4") (pintype "tri_state"))
    )
    (net (code "44") (name "/HALL5_GND") (class "Default")
      (node (ref "A139_HALL5") (pin "P$3_4") (pinfunction "P$3_P$3_4") (pintype "bidirectional"))
      (node (ref "C55") (pin "2") (pinfunction "2_2") (pintype "passive"))
      (node (ref "HALL5_HEADER") (pin "P$1") (pinfunction "1_P$1") (pintype "passive"))
    )
    (net (code "45") (name "/HALL5_OUTPUT") (class "Default")
      (node (ref "HALL5") (pin "4") (pinfunction "4_4") (pintype "passive"))
      (node (ref "U$2") (pin "4") (pinfunction "X5_4") (pintype "input"))
    )
    (net (code "46") (name "/HALL5_VCC") (class "Default")
      (node (ref "A139_HALL5") (pin "P$1") (pinfunction "P$1_P$1") (pintype "bidirectional"))
      (node (ref "A139_HALL5") (pin "P$6") (pinfunction "P$6_P$6") (pintype "bidirectional"))
      (node (ref "C55") (pin "1") (pinfunction "1_1") (pintype "passive"))
      (node (ref "HALL5_HEADER") (pin "P$2") (pinfunction "2_P$2") (pintype "passive"))
    )
    (net (code "47") (name "/HALL5_VOUT") (class "Default")
      (node (ref "A139_HALL5") (pin "P$2") (pinfunction "P$2_P$2") (pintype "bidirectional"))
      (node (ref "HALL5_HEADER") (pin "P$3") (pinfunction "3_P$3") (pintype "passive"))
    )
    (net (code "48") (name "/HALL5_~{SLEEP_IN}") (class "Default")
      (node (ref "HALL5_HEADER") (pin "P$4") (pinfunction "4_P$4") (pintype "passive"))
      (node (ref "R55") (pin "1") (pinfunction "1_1") (pintype "passive"))
    )
    (net (code "49") (name "/HALL5_~{SLEEP}") (class "Default")
      (node (ref "HALL5") (pin "3") (pinfunction "3_3") (pintype "passive"))
      (node (ref "SHIFT_0") (pin "5") (pinfunction "QF_5") (pintype "tri_state"))
    )
    (net (code "50") (name "/HALL6_GND") (class "Default")
      (node (ref "A139_HALL6") (pin "P$3_4") (pinfunction "P$3_P$3_4") (pintype "bidirectional"))
      (node (ref "C56") (pin "2") (pinfunction "2_2") (pintype "passive"))
      (node (ref "HALL6_HEADER") (pin "P$1") (pinfunction "1_P$1") (pintype "passive"))
    )
    (net (code "51") (name "/HALL6_OUTPUT") (class "Default")
      (node (ref "HALL6") (pin "4") (pinfunction "4_4") (pintype "passive"))
      (node (ref "U$2") (pin "3") (pinfunction "X6_3") (pintype "input"))
    )
    (net (code "52") (name "/HALL6_VCC") (class "Default")
      (node (ref "A139_HALL6") (pin "P$1") (pinfunction "P$1_P$1") (pintype "bidirectional"))
      (node (ref "A139_HALL6") (pin "P$6") (pinfunction "P$6_P$6") (pintype "bidirectional"))
      (node (ref "C56") (pin "1") (pinfunction "1_1") (pintype "passive"))
      (node (ref "HALL6_HEADER") (pin "P$2") (pinfunction "2_P$2") (pintype "passive"))
    )
    (net (code "53") (name "/HALL6_VOUT") (class "Default")
      (node (ref "A139_HALL6") (pin "P$2") (pinfunction "P$2_P$2") (pintype "bidirectional"))
      (node (ref "HALL6_HEADER") (pin "P$3") (pinfunction "3_P$3") (pintype "passive"))
    )
    (net (code "54") (name "/HALL6_~{SLEEP_IN}") (class "Default")
      (node (ref "HALL6_HEADER") (pin "P$4") (pinfunction "4_P$4") (pintype "passive"))
      (node (ref "R56") (pin "1") (pinfunction "1_1") (pintype "passive"))
    )
    (net (code "55") (name "/HALL6_~{SLEEP}") (class "Default")
      (node (ref "HALL6") (pin "3") (pinfunction "3_3") (pintype "passive"))
      (node (ref "SHIFT_0") (pin "6") (pinfunction "QG_6") (pintype "tri_state"))
    )
    (net (code "56") (name "/HALL7_GND") (class "Default")
      (node (ref "A139_HALL7") (pin "P$3_4") (pinfunction "P$3_P$3_4") (pintype "bidirectional"))
      (node (ref "C57") (pin "2") (pinfunction "2_2") (pintype "passive"))
      (node (ref "HALL7_HEADER") (pin "P$1") (pinfunction "1_P$1") (pintype "passive"))
    )
    (net (code "57") (name "/HALL7_OUTPUT") (class "Default")
      (node (ref "HALL7") (pin "4") (pinfunction "4_4") (pintype "passive"))
      (node (ref "U$2") (pin "2") (pinfunction "X7_2") (pintype "input"))
    )
    (net (code "58") (name "/HALL7_VCC") (class "Default")
      (node (ref "A139_HALL7") (pin "P$1") (pinfunction "P$1_P$1") (pintype "bidirectional"))
      (node (ref "A139_HALL7") (pin "P$6") (pinfunction "P$6_P$6") (pintype "bidirectional"))
      (node (ref "C57") (pin "1") (pinfunction "1_1") (pintype "passive"))
      (node (ref "HALL7_HEADER") (pin "P$2") (pinfunction "2_P$2") (pintype "passive"))
    )
    (net (code "59") (name "/HALL7_VOUT") (class "Default")
      (node (ref "A139_HALL7") (pin "P$2") (pinfunction "P$2_P$2") (pintype "bidirectional"))
      (node (ref "HALL7_HEADER") (pin "P$3") (pinfunction "3_P$3") (pintype "passive"))
    )
    (net (code "60") (name "/HALL7_~{SLEEP_IN}") (class "Default")
      (node (ref "HALL7_HEADER") (pin "P$4") (pinfunction "4_P$4") (pintype "passive"))
      (node (ref "R57") (pin "1") (pinfunction "1_1") (pintype "passive"))
    )
    (net (code "61") (name "/HALL7_~{SLEEP}") (class "Default")
      (node (ref "HALL7") (pin "3") (pinfunction "3_3") (pintype "passive"))
      (node (ref "SHIFT_0") (pin "7") (pinfunction "QH_7") (pintype "tri_state"))
    )
    (net (code "62") (name "/HALL8_GND") (class "Default")
      (node (ref "A139_HALL8") (pin "P$3_4") (pinfunction "P$3_P$3_4") (pintype "bidirectional"))
      (node (ref "C58") (pin "2") (pinfunction "2_2") (pintype "passive"))
      (node (ref "HALL8_HEADER") (pin "P$1") (pinfunction "1_P$1") (pintype "passive"))
    )
    (net (code "63") (name "/HALL8_OUTPUT") (class "Default")
      (node (ref "HALL8") (pin "4") (pinfunction "4_4") (pintype "passive"))
      (node (ref "U$2") (pin "23") (pinfunction "X8_23") (pintype "input"))
    )
    (net (code "64") (name "/HALL8_VCC") (class "Default")
      (node (ref "A139_HALL8") (pin "P$1") (pinfunction "P$1_P$1") (pintype "bidirectional"))
      (node (ref "A139_HALL8") (pin "P$6") (pinfunction "P$6_P$6") (pintype "bidirectional"))
      (node (ref "C58") (pin "1") (pinfunction "1_1") (pintype "passive"))
      (node (ref "HALL8_HEADER") (pin "P$2") (pinfunction "2_P$2") (pintype "passive"))
    )
    (net (code "65") (name "/HALL8_VOUT") (class "Default")
      (node (ref "A139_HALL8") (pin "P$2") (pinfunction "P$2_P$2") (pintype "bidirectional"))
      (node (ref "HALL8_HEADER") (pin "P$3") (pinfunction "3_P$3") (pintype "passive"))
    )
    (net (code "66") (name "/HALL8_~{SLEEP_IN}") (class "Default")
      (node (ref "HALL8_HEADER") (pin "P$4") (pinfunction "4_P$4") (pintype "passive"))
      (node (ref "R58") (pin "1") (pinfunction "1_1") (pintype "passive"))
    )
    (net (code "67") (name "/HALL8_~{SLEEP}") (class "Default")
      (node (ref "HALL8") (pin "3") (pinfunction "3_3") (pintype "passive"))
      (node (ref "SHIFT_1") (pin "15") (pinfunction "QA_15") (pintype "tri_state"))
    )
    (net (code "68") (name "/HALL9_GND") (class "Default")
      (node (ref "A139_HALL9") (pin "P$3_4") (pinfunction "P$3_P$3_4") (pintype "bidirectional"))
      (node (ref "C59") (pin "2") (pinfunction "2_2") (pintype "passive"))
      (node (ref "HALL9_HEADER") (pin "P$1") (pinfunction "1_P$1") (pintype "passive"))
    )
    (net (code "69") (name "/HALL9_OUTPUT") (class "Default")
      (node (ref "HALL9") (pin "4") (pinfunction "4_4") (pintype "passive"))
      (node (ref "U$2") (pin "22") (pinfunction "X9_22") (pintype "input"))
    )
    (net (code "70") (name "/HALL9_VCC") (class "Default")
      (node (ref "A139_HALL9") (pin "P$1") (pinfunction "P$1_P$1") (pintype "bidirectional"))
      (node (ref "A139_HALL9") (pin "P$6") (pinfunction "P$6_P$6") (pintype "bidirectional"))
      (node (ref "C59") (pin "1") (pinfunction "1_1") (pintype "passive"))
      (node (ref "HALL9_HEADER") (pin "P$2") (pinfunction "2_P$2") (pintype "passive"))
    )
    (net (code "71") (name "/HALL9_VOUT") (class "Default")
      (node (ref "A139_HALL9") (pin "P$2") (pinfunction "P$2_P$2") (pintype "bidirectional"))
      (node (ref "HALL9_HEADER") (pin "P$3") (pinfunction "3_P$3") (pintype "passive"))
    )
    (net (code "72") (name "/HALL9_~{SLEEP_IN}") (class "Default")
      (node (ref "HALL9_HEADER") (pin "P$4") (pinfunction "4_P$4") (pintype "passive"))
      (node (ref "R59") (pin "1") (pinfunction "1_1") (pintype "passive"))
    )
    (net (code "73") (name "/HALL9_~{SLEEP}") (class "Default")
      (node (ref "HALL9") (pin "3") (pinfunction "3_3") (pintype "passive"))
      (node (ref "SHIFT_1") (pin "1") (pinfunction "QB_1") (pintype "tri_state"))
    )
    (net (code "74") (name "/HALL10_GND") (class "Default")
      (node (ref "A139_HALL10") (pin "P$3_4") (pinfunction "P$3_P$3_4") (pintype "bidirectional"))
      (node (ref "C60") (pin "2") (pinfunction "2_2") (pintype "passive"))
      (node (ref "HALL10_HEADER") (pin "P$1") (pinfunction "1_P$1") (pintype "passive"))
    )
    (net (code "75") (name "/HALL10_OUTPUT") (class "Default")
      (node (ref "HALL10") (pin "4") (pinfunction "4_4") (pintype "passive"))
      (node (ref "U$2") (pin "21") (pinfunction "X10_21") (pintype "input"))
    )
    (net (code "76") (name "/HALL10_VCC") (class "Default")
      (node (ref "A139_HALL10") (pin "P$1") (pinfunction "P$1_P$1") (pintype "bidirectional"))
      (node (ref "A139_HALL10") (pin "P$6") (pinfunction "P$6_P$6") (pintype "bidirectional"))
      (node (ref "C60") (pin "1") (pinfunction "1_1") (pintype "passive"))
      (node (ref "HALL10_HEADER") (pin "P$2") (pinfunction "2_P$2") (pintype "passive"))
    )
    (net (code "77") (name "/HALL10_VOUT") (class "Default")
      (node (ref "A139_HALL10") (pin "P$2") (pinfunction "P$2_P$2") (pintype "bidirectional"))
      (node (ref "HALL10_HEADER") (pin "P$3") (pinfunction "3_P$3") (pintype "passive"))
    )
    (net (code "78") (name "/HALL10_~{SLEEP_IN}") (class "Default")
      (node (ref "HALL10_HEADER") (pin "P$4") (pinfunction "4_P$4") (pintype "passive"))
      (node (ref "R60") (pin "1") (pinfunction "1_1") (pintype "passive"))
    )
    (net (code "79") (name "/HALL10_~{SLEEP}") (class "Default")
      (node (ref "HALL10") (pin "3") (pinfunction "3_3") (pintype "passive"))
      (node (ref "SHIFT_1") (pin "2") (pinfunction "QC_2") (pintype "tri_state"))
    )
    (net (code "80") (name "/HALL11_GND") (class "Default")
      (node (ref "A139_HALL11") (pin "P$3_4") (pinfunction "P$3_P$3_4") (pintype "bidirectional"))
      (node (ref "C61") (pin "2") (pinfunction "2_2") (pintype "passive"))
      (node (ref "HALL11_HEADER") (pin "P$1") (pinfunction "1_P$1") (pintype "passive"))
    )
    (net (code "81") (name "/HALL11_OUTPUT") (class "Default")
      (node (ref "HALL11") (pin "4") (pinfunction "4_4") (pintype "passive"))
      (node (ref "U$2") (pin "20") (pinfunction "X11_20") (pintype "input"))
    )
    (net (code "82") (name "/HALL11_VCC") (class "Default")
      (node (ref "A139_HALL11") (pin "P$1") (pinfunction "P$1_P$1") (pintype "bidirectional"))
      (node (ref "A139_HALL11") (pin "P$6") (pinfunction "P$6_P$6") (pintype "bidirectional"))
      (node (ref "C61") (pin "1") (pinfunction "1_1") (pintype "passive"))
      (node (ref "HALL11_HEADER") (pin "P$2") (pinfunction "2_P$2") (pintype "passive"))
    )
    (net (code "83") (name "/HALL11_VOUT") (class "Default")
      (node (ref "A139_HALL11") (pin "P$2") (pinfunction "P$2_P$2") (pintype "bidirectional"))
      (node (ref "HALL11_HEADER") (pin "P$3") (pinfunction "3_P$3") (pintype "passive"))
    )
    (net (code "84") (name "/HALL11_~{SLEEP_IN}") (class "Default")
      (node (ref "HALL11_HEADER") (pin "P$4") (pinfunction "4_P$4") (pintype "passive"))
      (node (ref "R61") (pin "1") (pinfunction "1_1") (pintype "passive"))
    )
    (net (code "85") (name "/HALL11_~{SLEEP}") (class "Default")
      (node (ref "HALL11") (pin "3") (pinfunction "3_3") (pintype "passive"))
      (node (ref "SHIFT_1") (pin "3") (pinfunction "QD_3") (pintype "tri_state"))
    )
    (net (code "86") (name "/HALL12_GND") (class "Default")
      (node (ref "A139_HALL12") (pin "P$3_4") (pinfunction "P$3_P$3_4") (pintype "bidirectional"))
      (node (ref "C62") (pin "2") (pinfunction "2_2") (pintype "passive"))
      (node (ref "HALL12_HEADER") (pin "P$1") (pinfunction "1_P$1") (pintype "passive"))
    )
    (net (code "87") (name "/HALL12_OUTPUT") (class "Default")
      (node (ref "HALL12") (pin "4") (pinfunction "4_4") (pintype "passive"))
      (node (ref "U$2") (pin "19") (pinfunction "X12_19") (pintype "input"))
    )
    (net (code "88") (name "/HALL12_VCC") (class "Default")
      (node (ref "A139_HALL12") (pin "P$1") (pinfunction "P$1_P$1") (pintype "bidirectional"))
      (node (ref "A139_HALL12") (pin "P$6") (pinfunction "P$6_P$6") (pintype "bidirectional"))
      (node (ref "C62") (pin "1") (pinfunction "1_1") (pintype "passive"))
      (node (ref "HALL12_HEADER") (pin "P$2") (pinfunction "2_P$2") (pintype "passive"))
    )
    (net (code "89") (name "/HALL12_VOUT") (class "Default")
      (node (ref "A139_HALL12") (pin "P$2") (pinfunction "P$2_P$2") (pintype "bidirectional"))
      (node (ref "HALL12_HEADER") (pin "P$3") (pinfunction "3_P$3") (pintype "passive"))
    )
    (net (code "90") (name "/HALL12_~{SLEEP_IN}") (class "Default")
      (node (ref "HALL12_HEADER") (pin "P$4") (pinfunction "4_P$4") (pintype "passive"))
      (node (ref "R62") (pin "1") (pinfunction "1_1") (pintype "passive"))
    )
    (net (code "91") (name "/HALL12_~{SLEEP}") (class "Default")
      (node (ref "HALL12") (pin "3") (pinfunction "3_3") (pintype "passive"))
      (node (ref "SHIFT_1") (pin "4") (pinfunction "QE_4") (pintype "tri_state"))
    )
    (net (code "92") (name "/HALL13_GND") (class "Default")
      (node (ref "A139_HALL13") (pin "P$3_4") (pinfunction "P$3_P$3_4") (pintype "bidirectional"))
      (node (ref "C63") (pin "2") (pinfunction "2_2") (pintype "passive"))
      (node (ref "HALL13_HEADER") (pin "P$1") (pinfunction "1_P$1") (pintype "passive"))
    )
    (net (code "93") (name "/HALL13_OUTPUT") (class "Default")
      (node (ref "HALL13") (pin "4") (pinfunction "4_4") (pintype "passive"))
      (node (ref "U$2") (pin "18") (pinfunction "X13_18") (pintype "input"))
    )
    (net (code "94") (name "/HALL13_VCC") (class "Default")
      (node (ref "A139_HALL13") (pin "P$1") (pinfunction "P$1_P$1") (pintype "bidirectional"))
      (node (ref "A139_HALL13") (pin "P$6") (pinfunction "P$6_P$6") (pintype "bidirectional"))
      (node (ref "C63") (pin "1") (pinfunction "1_1") (pintype "passive"))
      (node (ref "HALL13_HEADER") (pin "P$2") (pinfunction "2_P$2") (pintype "passive"))
    )
    (net (code "95") (name "/HALL13_VOUT") (class "Default")
      (node (ref "A139_HALL13") (pin "P$2") (pinfunction "P$2_P$2") (pintype "bidirectional"))
      (node (ref "HALL13_HEADER") (pin "P$3") (pinfunction "3_P$3") (pintype "passive"))
    )
    (net (code "96") (name "/HALL13_~{SLEEP_IN}") (class "Default")
      (node (ref "HALL13_HEADER") (pin "P$4") (pinfunction "4_P$4") (pintype "passive"))
      (node (ref "R63") (pin "1") (pinfunction "1_1") (pintype "passive"))
    )
    (net (code "97") (name "/HALL13_~{SLEEP}") (class "Default")
      (node (ref "HALL13") (pin "3") (pinfunction "3_3") (pintype "passive"))
      (node (ref "SHIFT_1") (pin "5") (pinfunction "QF_5") (pintype "tri_state"))
    )
    (net (code "98") (name "/HALL14_GND") (class "Default")
      (node (ref "A139_HALL14") (pin "P$3_4") (pinfunction "P$3_P$3_4") (pintype "bidirectional"))
      (node (ref "C64") (pin "2") (pinfunction "2_2") (pintype "passive"))
      (node (ref "HALL14_HEADER") (pin "P$1") (pinfunction "1_P$1") (pintype "passive"))
    )
    (net (code "99") (name "/HALL14_OUTPUT") (class "Default")
      (node (ref "HALL14") (pin "4") (pinfunction "4_4") (pintype "passive"))
      (node (ref "U$2") (pin "17") (pinfunction "X14_17") (pintype "input"))
    )
    (net (code "100") (name "/HALL14_VCC") (class "Default")
      (node (ref "A139_HALL14") (pin "P$1") (pinfunction "P$1_P$1") (pintype "bidirectional"))
      (node (ref "A139_HALL14") (pin "P$6") (pinfunction "P$6_P$6") (pintype "bidirectional"))
      (node (ref "C64") (pin "1") (pinfunction "1_1") (pintype "passive"))
      (node (ref "HALL14_HEADER") (pin "P$2") (pinfunction "2_P$2") (pintype "passive"))
    )
    (net (code "101") (name "/HALL14_VOUT") (class "Default")
      (node (ref "A139_HALL14") (pin "P$2") (pinfunction "P$2_P$2") (pintype "bidirectional"))
      (node (ref "HALL14_HEADER") (pin "P$3") (pinfunction "3_P$3") (pintype "passive"))
    )
    (net (code "102") (name "/HALL14_~{SLEEP_IN}") (class "Default")
      (node (ref "HALL14_HEADER") (pin "P$4") (pinfunction "4_P$4") (pintype "passive"))
      (node (ref "R64") (pin "1") (pinfunction "1_1") (pintype "passive"))
    )
    (net (code "103") (name "/HALL14_~{SLEEP}") (class "Default")
      (node (ref "HALL14") (pin "3") (pinfunction "3_3") (pintype "passive"))
      (node (ref "SHIFT_1") (pin "6") (pinfunction "QG_6") (pintype "tri_state"))
    )
    (net (code "104") (name "/HALL15_GND") (class "Default")
      (node (ref "A139_HALL15") (pin "P$3_4") (pinfunction "P$3_P$3_4") (pintype "bidirectional"))
      (node (ref "C65") (pin "2") (pinfunction "2_2") (pintype "passive"))
      (node (ref "HALL15_HEADER") (pin "P$1") (pinfunction "1_P$1") (pintype "passive"))
    )
    (net (code "105") (name "/HALL15_OUTPUT") (class "Default")
      (node (ref "HALL15") (pin "4") (pinfunction "4_4") (pintype "passive"))
      (node (ref "U$2") (pin "16") (pinfunction "X15_16") (pintype "input"))
    )
    (net (code "106") (name "/HALL15_VCC") (class "Default")
      (node (ref "A139_HALL15") (pin "P$1") (pinfunction "P$1_P$1") (pintype "bidirectional"))
      (node (ref "A139_HALL15") (pin "P$6") (pinfunction "P$6_P$6") (pintype "bidirectional"))
      (node (ref "C65") (pin "1") (pinfunction "1_1") (pintype "passive"))
      (node (ref "HALL15_HEADER") (pin "P$2") (pinfunction "2_P$2") (pintype "passive"))
    )
    (net (code "107") (name "/HALL15_VOUT") (class "Default")
      (node (ref "A139_HALL15") (pin "P$2") (pinfunction "P$2_P$2") (pintype "bidirectional"))
      (node (ref "HALL15_HEADER") (pin "P$3") (pinfunction "3_P$3") (pintype "passive"))
    )
    (net (code "108") (name "/HALL15_~{SLEEP_IN}") (class "Default")
      (node (ref "HALL15_HEADER") (pin "P$4") (pinfunction "4_P$4") (pintype "passive"))
      (node (ref "R65") (pin "1") (pinfunction "1_1") (pintype "passive"))
    )
    (net (code "109") (name "/HALL15_~{SLEEP}") (class "Default")
      (node (ref "HALL15") (pin "3") (pinfunction "3_3") (pintype "passive"))
      (node (ref "SHIFT_1") (pin "7") (pinfunction "QH_7") (pintype "tri_state"))
    )
    (net (code "110") (name "/HALL16_GND") (class "Default")
      (node (ref "A139_HALL16") (pin "P$3_4") (pinfunction "P$3_P$3_4") (pintype "bidirectional"))
      (node (ref "C66") (pin "2") (pinfunction "2_2") (pintype "passive"))
      (node (ref "HALL16_HEADER") (pin "P$1") (pinfunction "1_P$1") (pintype "passive"))
    )
    (net (code "111") (name "/HALL16_VCC") (class "Default")
      (node (ref "A139_HALL16") (pin "P$1") (pinfunction "P$1_P$1") (pintype "bidirectional"))
      (node (ref "A139_HALL16") (pin "P$6") (pinfunction "P$6_P$6") (pintype "bidirectional"))
      (node (ref "C66") (pin "1") (pinfunction "1_1") (pintype "passive"))
      (node (ref "HALL16_HEADER") (pin "P$2") (pinfunction "2_P$2") (pintype "passive"))
    )
    (net (code "112") (name "/HALL16_VOUT") (class "Default")
      (node (ref "A139_HALL16") (pin "P$2") (pinfunction "P$2_P$2") (pintype "bidirectional"))
      (node (ref "HALL16_HEADER") (pin "P$3") (pinfunction "3_P$3") (pintype "passive"))
    )
    (net (code "113") (name "/HALL16_~{SLEEP_IN}") (class "Default")
      (node (ref "HALL16_HEADER") (pin "P$4") (pinfunction "4_P$4") (pintype "passive"))
      (node (ref "R66") (pin "1") (pinfunction "1_1") (pintype "passive"))
    )
    (net (code "114") (name "/HALL17_GND") (class "Default")
      (node (ref "A139_HALL17") (pin "P$3_4") (pinfunction "P$3_P$3_4") (pintype "bidirectional"))
      (node (ref "C67") (pin "2") (pinfunction "2_2") (pintype "passive"))
      (node (ref "HALL17_HEADER") (pin "P$1") (pinfunction "1_P$1") (pintype "passive"))
    )
    (net (code "115") (name "/HALL17_VCC") (class "Default")
      (node (ref "A139_HALL17") (pin "P$1") (pinfunction "P$1_P$1") (pintype "bidirectional"))
      (node (ref "A139_HALL17") (pin "P$6") (pinfunction "P$6_P$6") (pintype "bidirectional"))
      (node (ref "C67") (pin "1") (pinfunction "1_1") (pintype "passive"))
      (node (ref "HALL17_HEADER") (pin "P$2") (pinfunction "2_P$2") (pintype "passive"))
    )
    (net (code "116") (name "/HALL17_VOUT") (class "Default")
      (node (ref "A139_HALL17") (pin "P$2") (pinfunction "P$2_P$2") (pintype "bidirectional"))
      (node (ref "HALL17_HEADER") (pin "P$3") (pinfunction "3_P$3") (pintype "passive"))
    )
    (net (code "117") (name "/HALL17_~{SLEEP_IN}") (class "Default")
      (node (ref "HALL17_HEADER") (pin "P$4") (pinfunction "4_P$4") (pintype "passive"))
      (node (ref "R67") (pin "1") (pinfunction "1_1") (pintype "passive"))
    )
    (net (code "118") (name "/HALL18_GND") (class "Default")
      (node (ref "A139_HALL18") (pin "P$3_4") (pinfunction "P$3_P$3_4") (pintype "bidirectional"))
      (node (ref "C68") (pin "2") (pinfunction "2_2") (pintype "passive"))
      (node (ref "HALL18_HEADER") (pin "P$1") (pinfunction "1_P$1") (pintype "passive"))
    )
    (net (code "119") (name "/HALL18_VCC") (class "Default")
      (node (ref "A139_HALL18") (pin "P$1") (pinfunction "P$1_P$1") (pintype "bidirectional"))
      (node (ref "A139_HALL18") (pin "P$6") (pinfunction "P$6_P$6") (pintype "bidirectional"))
      (node (ref "C68") (pin "1") (pinfunction "1_1") (pintype "passive"))
      (node (ref "HALL18_HEADER") (pin "P$2") (pinfunction "2_P$2") (pintype "passive"))
    )
    (net (code "120") (name "/HALL18_VOUT") (class "Default")
      (node (ref "A139_HALL18") (pin "P$2") (pinfunction "P$2_P$2") (pintype "bidirectional"))
      (node (ref "HALL18_HEADER") (pin "P$3") (pinfunction "3_P$3") (pintype "passive"))
    )
    (net (code "121") (name "/HALL18_~{SLEEP_IN}") (class "Default")
      (node (ref "HALL18_HEADER") (pin "P$4") (pinfunction "4_P$4") (pintype "passive"))
      (node (ref "R68") (pin "1") (pinfunction "1_1") (pintype "passive"))
    )
    (net (code "122") (name "/HALL19_GND") (class "Default")
      (node (ref "A139_HALL19") (pin "P$3_4") (pinfunction "P$3_P$3_4") (pintype "bidirectional"))
      (node (ref "C69") (pin "2") (pinfunction "2_2") (pintype "passive"))
      (node (ref "HALL19_HEADER") (pin "P$1") (pinfunction "1_P$1") (pintype "passive"))
    )
    (net (code "123") (name "/HALL19_VCC") (class "Default")
      (node (ref "A139_HALL19") (pin "P$1") (pinfunction "P$1_P$1") (pintype "bidirectional"))
      (node (ref "A139_HALL19") (pin "P$6") (pinfunction "P$6_P$6") (pintype "bidirectional"))
      (node (ref "C69") (pin "1") (pinfunction "1_1") (pintype "passive"))
      (node (ref "HALL19_HEADER") (pin "P$2") (pinfunction "2_P$2") (pintype "passive"))
    )
    (net (code "124") (name "/HALL19_VOUT") (class "Default")
      (node (ref "A139_HALL19") (pin "P$2") (pinfunction "P$2_P$2") (pintype "bidirectional"))
      (node (ref "HALL19_HEADER") (pin "P$3") (pinfunction "3_P$3") (pintype "passive"))
    )
    (net (code "125") (name "/HALL19_~{SLEEP_IN}") (class "Default")
      (node (ref "HALL19_HEADER") (pin "P$4") (pinfunction "4_P$4") (pintype "passive"))
      (node (ref "R69") (pin "1") (pinfunction "1_1") (pintype "passive"))
    )
    (net (code "126") (name "/LED_GRN") (class "Default")
      (node (ref "R2") (pin "2") (pinfunction "2_2") (pintype "passive"))
      (node (ref "U1") (pin "26") (pinfunction "PC3(ADC3)_26") (pintype "bidirectional"))
    )
    (net (code "127") (name "/LED_RED") (class "Default")
      (node (ref "R1") (pin "2") (pinfunction "2_2") (pintype "passive"))
      (node (ref "U1") (pin "2") (pinfunction "PD4(XCK/T0)_2") (pintype "bidirectional"))
    )
    (net (code "128") (name "/MISO") (class "Default")
      (node (ref "J1") (pin "1") (pinfunction "1_1") (pintype "passive"))
      (node (ref "U$1") (pin "MISO7") (pinfunction "DATA_OUT_MISO_MISO7") (pintype "output"))
      (node (ref "U1") (pin "16") (pinfunction "PB4(MISO)_16") (pintype "bidirectional"))
    )
    (net (code "129") (name "/MOSI") (class "Default")
      (node (ref "J1") (pin "4") (pinfunction "4_4") (pintype "passive"))
      (node (ref "SHIFT_0") (pin "14") (pinfunction "SER_14") (pintype "input"))
      (node (ref "U$1") (pin "MOSI3") (pinfunction "DATA_IN_MOSI_MOSI3") (pintype "input"))
      (node (ref "U1") (pin "15") (pinfunction "PB3(MOSI/OC2)_15") (pintype "bidirectional"))
    )
    (net (code "130") (name "/MUX_S0") (class "Default")
      (node (ref "U$2") (pin "10") (pinfunction "S0_10") (pintype "input"))
      (node (ref "U1") (pin "13") (pinfunction "PB1(OC1A)_13") (pintype "bidirectional"))
    )
    (net (code "131") (name "/MUX_S1") (class "Default")
      (node (ref "U$2") (pin "11") (pinfunction "S1_11") (pintype "input"))
      (node (ref "U1") (pin "9") (pinfunction "PD5(T1)_9") (pintype "bidirectional"))
    )
    (net (code "132") (name "/MUX_S2") (class "Default")
      (node (ref "U$2") (pin "14") (pinfunction "S2_14") (pintype "input"))
      (node (ref "U1") (pin "10") (pinfunction "PD6(AIN0)_10") (pintype "bidirectional"))
    )
    (net (code "133") (name "/MUX_S3") (class "Default")
      (node (ref "U$2") (pin "13") (pinfunction "S3_13") (pintype "input"))
      (node (ref "U1") (pin "11") (pinfunction "PD7(AIN1)_11") (pintype "bidirectional"))
    )
    (net (code "134") (name "/MUX_~{EN}") (class "Default")
      (node (ref "R28") (pin "1") (pinfunction "1_1") (pintype "passive"))
      (node (ref "U$2") (pin "15") (pinfunction "~{E}_15") (pintype "input"))
      (node (ref "U1") (pin "12") (pinfunction "PB0(ICP)_12") (pintype "bidirectional"))
    )
    (net (code "135") (name "/PB7") (class "Default")
      (node (ref "PB7") (pin "1") (pinfunction "P$1_1") (pintype "bidirectional"))
      (node (ref "U1") (pin "8") (pinfunction "PB7(XTAL2/TOSC2)_8") (pintype "bidirectional"))
    )
    (net (code "136") (name "/RESET") (class "Default")
      (node (ref "C5") (pin "2") (pinfunction "2_2") (pintype "passive"))
      (node (ref "J1") (pin "5") (pinfunction "5_5") (pintype "passive"))
      (node (ref "R6") (pin "1") (pinfunction "1_1") (pintype "passive"))
      (node (ref "RESET") (pin "S$1") (pinfunction "S1_S$1") (pintype "passive"))
      (node (ref "U$3") (pin "1") (pinfunction "P$1_1") (pintype "bidirectional"))
      (node (ref "U1") (pin "29") (pinfunction "PC6(/RESET)_29") (pintype "bidirectional"))
    )
    (net (code "137") (name "/SCK") (class "Default")
      (node (ref "J1") (pin "3") (pinfunction "3_3") (pintype "passive"))
      (node (ref "SHIFT_0") (pin "11") (pinfunction "SRCLK_11") (pintype "input"))
      (node (ref "SHIFT_1") (pin "11") (pinfunction "SRCLK_11") (pintype "input"))
      (node (ref "U$1") (pin "SCK5") (pinfunction "SCLK_SCK5") (pintype "input"))
      (node (ref "U1") (pin "17") (pinfunction "PB5(SCK)_17") (pintype "bidirectional"))
    )
    (net (code "138") (name "/SCL") (class "Default")
      (node (ref "DS3231M") (pin "8") (pinfunction "P$8_SCL_8") (pintype "bidirectional"))
      (node (ref "OLED") (pin "3") (pinfunction "3_3") (pintype "passive"))
      (node (ref "R7") (pin "1") (pinfunction "1_1") (pintype "passive"))
      (node (ref "U1") (pin "28") (pinfunction "PC5(ADC5/SCL)_28") (pintype "bidirectional"))
    )
    (net (code "139") (name "/SDA") (class "Default")
      (node (ref "DS3231M") (pin "7") (pinfunction "P$7_SDA_7") (pintype "bidirectional"))
      (node (ref "OLED") (pin "4") (pinfunction "4_4") (pintype "passive"))
      (node (ref "R8") (pin "1") (pinfunction "1_1") (pintype "passive"))
      (node (ref "U1") (pin "27") (pinfunction "PC4(ADC4/SDA)_27") (pintype "bidirectional"))
    )
    (net (code "140") (name "/SHIFT_CLEAR") (class "Default")
      (node (ref "R14") (pin "1") (pinfunction "1_1") (pintype "passive"))
      (node (ref "SHIFT_0") (pin "10") (pinfunction "~{SRCLR}_10") (pintype "input"))
      (node (ref "SHIFT_1") (pin "10") (pinfunction "~{SRCLR}_10") (pintype "input"))
      (node (ref "U1") (pin "24") (pinfunction "PC1(ADC1)_24") (pintype "bidirectional"))
    )
    (net (code "141") (name "/TO_FTDI_RX") (class "Default")
      (node (ref "JP1") (pin "5") (pinfunction "5_5") (pintype "passive"))
      (node (ref "U1") (pin "31") (pinfunction "PD1(TXD)_31") (pintype "bidirectional"))
    )
    (net (code "142") (name "/TO_FTDI_TX") (class "Default")
      (node (ref "JP1") (pin "4") (pinfunction "4_4") (pintype "passive"))
      (node (ref "U1") (pin "30") (pinfunction "PD0(RXD)_30") (pintype "bidirectional"))
    )
    (net (code "143") (name "/VBAT") (class "Default")
      (node (ref "CR1220_BATTERY") (pin "P$1") (pinfunction "VBAT_P$1") (pintype "power_in"))
      (node (ref "CR1220_BATTERY") (pin "P$2") (pinfunction "P$2_P$2") (pintype "power_in"))
      (node (ref "DS3231M") (pin "6") (pinfunction "P$6_VBAT_6") (pintype "bidirectional"))
    )
    (net (code "144") (name "/VBATTERY") (class "Default")
      (node (ref "LTC4411") (pin "1") (pinfunction "VIN_1") (pintype "passive"))
      (node (ref "MOLEX_KK") (pin "2") (pinfunction "S_2") (pintype "passive"))
      (node (ref "PRIMARY_BATTERY") (pin "VBAT") (pinfunction "VBAT_VBAT") (pintype "power_in"))
    )
    (net (code "145") (name "/VRAW") (class "Default")
      (node (ref "P-FET") (pin "2") (pinfunction "S_2") (pintype "passive"))
      (node (ref "R33") (pin "2") (pinfunction "2_2") (pintype "passive"))
    )
    (net (code "146") (name "/VRAW1") (class "Default")
      (node (ref "C25") (pin "1") (pinfunction "1_1") (pintype "passive"))
      (node (ref "LTC4411") (pin "5") (pinfunction "OUT_5") (pintype "passive"))
      (node (ref "PWR_JUMPER") (pin "2") (pinfunction "2_2") (pintype "passive"))
      (node (ref "PWR_PASSTHRU") (pin "2") (pinfunction "P$2_2") (pintype "bidirectional"))
      (node (ref "SCHOTTKY") (pin "C") (pinfunction "C_C") (pintype "passive"))
    )
    (net (code "147") (name "/VRAW2") (class "Default")
      (node (ref "C1") (pin "+") (pinfunction "+_+") (pintype "passive"))
      (node (ref "MCP1700T-3302") (pin "3") (pinfunction "VIN_3") (pintype "input"))
      (node (ref "PWR_JUMPER") (pin "1") (pinfunction "1_1") (pintype "passive"))
      (node (ref "PWR_PASSTHRU") (pin "1") (pinfunction "P$1_1") (pintype "bidirectional"))
    )
    (net (code "148") (name "/V_JACK") (class "Default")
      (node (ref "2,1MM_JACK") (pin "P$1") (pinfunction "PWR_P$1") (pintype "bidirectional"))
      (node (ref "SCHOTTKY") (pin "A") (pinfunction "A_A") (pintype "passive"))
    )
    (net (code "149") (name "/~{SLEEP0}") (class "Default")
      (node (ref "A139_HALL0") (pin "P$5") (pinfunction "P$5_P$5") (pintype "bidirectional"))
      (node (ref "R50") (pin "2") (pinfunction "2_2") (pintype "passive"))
    )
    (net (code "150") (name "/~{SLEEP1}") (class "Default")
      (node (ref "A139_HALL1") (pin "P$5") (pinfunction "P$5_P$5") (pintype "bidirectional"))
      (node (ref "R51") (pin "2") (pinfunction "2_2") (pintype "passive"))
    )
    (net (code "151") (name "/~{SLEEP2}") (class "Default")
      (node (ref "A139_HALL2") (pin "P$5") (pinfunction "P$5_P$5") (pintype "bidirectional"))
      (node (ref "R52") (pin "2") (pinfunction "2_2") (pintype "passive"))
    )
    (net (code "152") (name "/~{SLEEP3}") (class "Default")
      (node (ref "A139_HALL3") (pin "P$5") (pinfunction "P$5_P$5") (pintype "bidirectional"))
      (node (ref "R53") (pin "2") (pinfunction "2_2") (pintype "passive"))
    )
    (net (code "153") (name "/~{SLEEP4}") (class "Default")
      (node (ref "A139_HALL4") (pin "P$5") (pinfunction "P$5_P$5") (pintype "bidirectional"))
      (node (ref "R54") (pin "2") (pinfunction "2_2") (pintype "passive"))
    )
    (net (code "154") (name "/~{SLEEP5}") (class "Default")
      (node (ref "A139_HALL5") (pin "P$5") (pinfunction "P$5_P$5") (pintype "bidirectional"))
      (node (ref "R55") (pin "2") (pinfunction "2_2") (pintype "passive"))
    )
    (net (code "155") (name "/~{SLEEP6}") (class "Default")
      (node (ref "A139_HALL6") (pin "P$5") (pinfunction "P$5_P$5") (pintype "bidirectional"))
      (node (ref "R56") (pin "2") (pinfunction "2_2") (pintype "passive"))
    )
    (net (code "156") (name "/~{SLEEP7}") (class "Default")
      (node (ref "A139_HALL7") (pin "P$5") (pinfunction "P$5_P$5") (pintype "bidirectional"))
      (node (ref "R57") (pin "2") (pinfunction "2_2") (pintype "passive"))
    )
    (net (code "157") (name "/~{SLEEP8}") (class "Default")
      (node (ref "A139_HALL8") (pin "P$5") (pinfunction "P$5_P$5") (pintype "bidirectional"))
      (node (ref "R58") (pin "2") (pinfunction "2_2") (pintype "passive"))
    )
    (net (code "158") (name "/~{SLEEP9}") (class "Default")
      (node (ref "A139_HALL9") (pin "P$5") (pinfunction "P$5_P$5") (pintype "bidirectional"))
      (node (ref "R59") (pin "2") (pinfunction "2_2") (pintype "passive"))
    )
    (net (code "159") (name "/~{SLEEP10}") (class "Default")
      (node (ref "A139_HALL10") (pin "P$5") (pinfunction "P$5_P$5") (pintype "bidirectional"))
      (node (ref "R60") (pin "2") (pinfunction "2_2") (pintype "passive"))
    )
    (net (code "160") (name "/~{SLEEP11}") (class "Default")
      (node (ref "A139_HALL11") (pin "P$5") (pinfunction "P$5_P$5") (pintype "bidirectional"))
      (node (ref "R61") (pin "2") (pinfunction "2_2") (pintype "passive"))
    )
    (net (code "161") (name "/~{SLEEP12}") (class "Default")
      (node (ref "A139_HALL12") (pin "P$5") (pinfunction "P$5_P$5") (pintype "bidirectional"))
      (node (ref "R62") (pin "2") (pinfunction "2_2") (pintype "passive"))
    )
    (net (code "162") (name "/~{SLEEP13}") (class "Default")
      (node (ref "A139_HALL13") (pin "P$5") (pinfunction "P$5_P$5") (pintype "bidirectional"))
      (node (ref "R63") (pin "2") (pinfunction "2_2") (pintype "passive"))
    )
    (net (code "163") (name "/~{SLEEP14}") (class "Default")
      (node (ref "A139_HALL14") (pin "P$5") (pinfunction "P$5_P$5") (pintype "bidirectional"))
      (node (ref "R64") (pin "2") (pinfunction "2_2") (pintype "passive"))
    )
    (net (code "164") (name "/~{SLEEP15}") (class "Default")
      (node (ref "A139_HALL15") (pin "P$5") (pinfunction "P$5_P$5") (pintype "bidirectional"))
      (node (ref "R65") (pin "2") (pinfunction "2_2") (pintype "passive"))
    )
    (net (code "165") (name "/~{SLEEP16}") (class "Default")
      (node (ref "A139_HALL16") (pin "P$5") (pinfunction "P$5_P$5") (pintype "bidirectional"))
      (node (ref "R66") (pin "2") (pinfunction "2_2") (pintype "passive"))
    )
    (net (code "166") (name "/~{SLEEP17}") (class "Default")
      (node (ref "A139_HALL17") (pin "P$5") (pinfunction "P$5_P$5") (pintype "bidirectional"))
      (node (ref "R67") (pin "2") (pinfunction "2_2") (pintype "passive"))
    )
    (net (code "167") (name "/~{SLEEP18}") (class "Default")
      (node (ref "A139_HALL18") (pin "P$5") (pinfunction "P$5_P$5") (pintype "bidirectional"))
      (node (ref "R68") (pin "2") (pinfunction "2_2") (pintype "passive"))
    )
    (net (code "168") (name "/~{SLEEP19}") (class "Default")
      (node (ref "A139_HALL19") (pin "P$5") (pinfunction "P$5_P$5") (pintype "bidirectional"))
      (node (ref "R69") (pin "2") (pinfunction "2_2") (pintype "passive"))
    )
    (net (code "169") (name "GND") (class "Default")
      (node (ref "1") (pin "S$1") (pinfunction "S1_S$1") (pintype "passive"))
      (node (ref "2") (pin "S$1") (pinfunction "S1_S$1") (pintype "passive"))
      (node (ref "2,1MM_JACK") (pin "P$2") (pinfunction "GND_P$2") (pintype "bidirectional"))
      (node (ref "BJT") (pin "2") (pinfunction "E_2") (pintype "passive"))
      (node (ref "C1") (pin "-") (pinfunction "-_-") (pintype "passive"))
      (node (ref "C10") (pin "2") (pinfunction "2_2") (pintype "passive"))
      (node (ref "C2") (pin "-") (pinfunction "-_-") (pintype "passive"))
      (node (ref "C25") (pin "2") (pinfunction "2_2") (pintype "passive"))
      (node (ref "C3") (pin "2") (pinfunction "2_2") (pintype "passive"))
      (node (ref "C4") (pin "2") (pinfunction "2_2") (pintype "passive"))
      (node (ref "C6") (pin "2") (pinfunction "2_2") (pintype "passive"))
      (node (ref "C7") (pin "2") (pinfunction "2_2") (pintype "passive"))
      (node (ref "C8") (pin "2") (pinfunction "2_2") (pintype "passive"))
      (node (ref "C9") (pin "2") (pinfunction "2_2") (pintype "passive"))
      (node (ref "CR1220_BATTERY") (pin "GND") (pinfunction "GND_GND") (pintype "power_in"))
      (node (ref "DS3231M") (pin "5") (pinfunction "P$5_GND_5") (pintype "power_in"))
      (node (ref "GND") (pin "1") (pinfunction "P$1_1") (pintype "bidirectional"))
      (node (ref "GROUND_CON") (pin "1") (pinfunction "P$1_1") (pintype "bidirectional"))
      (node (ref "J1") (pin "6") (pinfunction "6_6") (pintype "passive"))
      (node (ref "JP1") (pin "1") (pinfunction "1_1") (pintype "passive"))
      (node (ref "JP1") (pin "2") (pinfunction "2_2") (pintype "passive"))
      (node (ref "LED1") (pin "C") (pinfunction "C_C") (pintype "passive"))
      (node (ref "LED2") (pin "C") (pinfunction "C_C") (pintype "passive"))
      (node (ref "LTC4411") (pin "2") (pinfunction "GND_2") (pintype "passive"))
      (node (ref "LTC4411") (pin "3") (pinfunction "CTL_3") (pintype "passive"))
      (node (ref "MCP1700T-3302") (pin "1") (pinfunction "GND_1") (pintype "passive"))
      (node (ref "MOLEX_KK") (pin "1") (pinfunction "S_1") (pintype "passive"))
      (node (ref "OLED") (pin "2") (pinfunction "2_2") (pintype "passive"))
      (node (ref "PRIMARY_BATTERY") (pin "GND") (pinfunction "GND_GND") (pintype "power_in"))
      (node (ref "R29") (pin "1") (pinfunction "1_1") (pintype "passive"))
      (node (ref "R3") (pin "1") (pinfunction "1_1") (pintype "passive"))
      (node (ref "R32") (pin "1") (pinfunction "1_1") (pintype "passive"))
      (node (ref "RESET") (pin "P$1") (pinfunction "P1_P$1") (pintype "passive"))
      (node (ref "SHIFT_0") (pin "13") (pinfunction "~{OE}_13") (pintype "input"))
      (node (ref "SHIFT_0") (pin "8") (pinfunction "GND_8") (pintype "power_in"))
      (node (ref "SHIFT_1") (pin "13") (pinfunction "~{OE}_13") (pintype "input"))
      (node (ref "SHIFT_1") (pin "8") (pinfunction "GND_8") (pintype "power_in"))
      (node (ref "U$1") (pin "GND6") (pinfunction "VSS_GND_GND6") (pintype "power_in"))
      (node (ref "U$1") (pin "MNT1") (pinfunction "GND1_MNT1") (pintype "power_in"))
      (node (ref "U$1") (pin "MNT2") (pinfunction "GND2_MNT2") (pintype "power_in"))
      (node (ref "U$1") (pin "MNT3") (pinfunction "GND3_MNT3") (pintype "power_in"))
      (node (ref "U$1") (pin "MNT4") (pinfunction "GND4_MNT4") (pintype "power_in"))
      (node (ref "U$2") (pin "12") (pinfunction "GND_12") (pintype "power_in"))
      (node (ref "U$4") (pin "1") (pinfunction "P$1_1") (pintype "bidirectional"))
      (node (ref "U$7") (pin "1") (pinfunction "P$1_1") (pintype "bidirectional"))
      (node (ref "U$9") (pin "1") (pinfunction "P$1_1") (pintype "bidirectional"))
      (node (ref "U1") (pin "3") (pinfunction "GND_3") (pintype "bidirectional"))
      (node (ref "U1") (pin "5") (pinfunction "GND_5") (pintype "bidirectional"))
    )
    (net (code "170") (name "Net-(BJT-B)") (class "Default")
      (node (ref "BJT") (pin "1") (pinfunction "B_1") (pintype "passive"))
      (node (ref "R31") (pin "2") (pinfunction "2_2") (pintype "passive"))
    )
    (net (code "171") (name "Net-(LED1-PadA)") (class "Default")
      (node (ref "LED1") (pin "A") (pinfunction "A_A") (pintype "passive"))
      (node (ref "R1") (pin "1") (pinfunction "1_1") (pintype "passive"))
    )
    (net (code "172") (name "Net-(LED2-PadA)") (class "Default")
      (node (ref "LED2") (pin "A") (pinfunction "A_A") (pintype "passive"))
      (node (ref "R2") (pin "1") (pinfunction "1_1") (pintype "passive"))
    )
    (net (code "173") (name "Net-(LTC4411-STAT)") (class "Default")
      (node (ref "LTC4411") (pin "4") (pinfunction "STAT_4") (pintype "passive"))
      (node (ref "R34") (pin "1") (pinfunction "1_1") (pintype "passive"))
    )
    (net (code "174") (name "Net-(P-FET-D)") (class "Default")
      (node (ref "P-FET") (pin "3") (pinfunction "D_3") (pintype "passive"))
      (node (ref "R30") (pin "2") (pinfunction "2_2") (pintype "passive"))
    )
    (net (code "175") (name "Net-(SHIFT_0-QH*)") (class "Default")
      (node (ref "SHIFT_0") (pin "9") (pinfunction "QH*_9") (pintype "tri_state"))
      (node (ref "SHIFT_1") (pin "14") (pinfunction "SER_14") (pintype "input"))
    )
    (net (code "176") (name "Net-(U$1-DAT1_NC)") (class "Default")
      (node (ref "R5") (pin "1") (pinfunction "1_1") (pintype "passive"))
      (node (ref "U$1") (pin "NC1") (pinfunction "DAT1_NC_NC1") (pintype "bidirectional"))
    )
    (net (code "177") (name "Net-(U$1-DAT2_RES)") (class "Default")
      (node (ref "R4") (pin "1") (pinfunction "1_1") (pintype "passive"))
      (node (ref "U$1") (pin "RES8") (pinfunction "DAT2_RES_RES8") (pintype "bidirectional"))
    )
    (net (code "178") (name "VCC") (class "Default")
      (node (ref "C10") (pin "1") (pinfunction "1_1") (pintype "passive"))
      (node (ref "C2") (pin "+") (pinfunction "+_+") (pintype "passive"))
      (node (ref "C3") (pin "1") (pinfunction "1_1") (pintype "passive"))
      (node (ref "C4") (pin "1") (pinfunction "1_1") (pintype "passive"))
      (node (ref "C6") (pin "1") (pinfunction "1_1") (pintype "passive"))
      (node (ref "C7") (pin "1") (pinfunction "1_1") (pintype "passive"))
      (node (ref "C8") (pin "1") (pinfunction "1_1") (pintype "passive"))
      (node (ref "C9") (pin "1") (pinfunction "1_1") (pintype "passive"))
      (node (ref "DS3231M") (pin "2") (pinfunction "P$2_VCC_2") (pintype "power_in"))
      (node (ref "HALL0") (pin "1") (pinfunction "1_1") (pintype "passive"))
      (node (ref "HALL1") (pin "1") (pinfunction "1_1") (pintype "passive"))
      (node (ref "HALL10") (pin "1") (pinfunction "1_1") (pintype "passive"))
      (node (ref "HALL11") (pin "1") (pinfunction "1_1") (pintype "passive"))
      (node (ref "HALL12") (pin "1") (pinfunction "1_1") (pintype "passive"))
      (node (ref "HALL13") (pin "1") (pinfunction "1_1") (pintype "passive"))
      (node (ref "HALL14") (pin "1") (pinfunction "1_1") (pintype "passive"))
      (node (ref "HALL15") (pin "1") (pinfunction "1_1") (pintype "passive"))
      (node (ref "HALL2") (pin "1") (pinfunction "1_1") (pintype "passive"))
      (node (ref "HALL3") (pin "1") (pinfunction "1_1") (pintype "passive"))
      (node (ref "HALL4") (pin "1") (pinfunction "1_1") (pintype "passive"))
      (node (ref "HALL5") (pin "1") (pinfunction "1_1") (pintype "passive"))
      (node (ref "HALL6") (pin "1") (pinfunction "1_1") (pintype "passive"))
      (node (ref "HALL7") (pin "1") (pinfunction "1_1") (pintype "passive"))
      (node (ref "HALL8") (pin "1") (pinfunction "1_1") (pintype "passive"))
      (node (ref "HALL9") (pin "1") (pinfunction "1_1") (pintype "passive"))
      (node (ref "INDUCTOR") (pin "P$2") (pinfunction "2_P$2") (pintype "passive"))
      (node (ref "J1") (pin "2") (pinfunction "2_2") (pintype "passive"))
      (node (ref "JP1") (pin "3") (pinfunction "3_3") (pintype "passive"))
      (node (ref "MCP1700T-3302") (pin "2") (pinfunction "VOUT_2") (pintype "output"))
      (node (ref "OLED") (pin "1") (pinfunction "1_1") (pintype "passive"))
      (node (ref "R14") (pin "2") (pinfunction "2_2") (pintype "passive"))
      (node (ref "R15") (pin "2") (pinfunction "2_2") (pintype "passive"))
      (node (ref "R28") (pin "2") (pinfunction "2_2") (pintype "passive"))
      (node (ref "R34") (pin "2") (pinfunction "2_2") (pintype "passive"))
      (node (ref "R4") (pin "2") (pinfunction "2_2") (pintype "passive"))
      (node (ref "R5") (pin "2") (pinfunction "2_2") (pintype "passive"))
      (node (ref "R6") (pin "2") (pinfunction "2_2") (pintype "passive"))
      (node (ref "R7") (pin "2") (pinfunction "2_2") (pintype "passive"))
      (node (ref "R8") (pin "2") (pinfunction "2_2") (pintype "passive"))
      (node (ref "R9") (pin "2") (pinfunction "2_2") (pintype "passive"))
      (node (ref "SHIFT_0") (pin "16") (pinfunction "VCC_16") (pintype "power_in"))
      (node (ref "SHIFT_1") (pin "16") (pinfunction "VCC_16") (pintype "power_in"))
      (node (ref "U$1") (pin "VDD4") (pinfunction "VDD_VDD4") (pintype "power_in"))
      (node (ref "U$2") (pin "24") (pinfunction "VCC_24") (pintype "power_in"))
      (node (ref "U1") (pin "4") (pinfunction "VCC_4") (pintype "bidirectional"))
      (node (ref "U1") (pin "6") (pinfunction "VCC_6") (pintype "bidirectional"))
    )
    (net (code "179") (name "unconnected-(1-PadP)") (class "Default")
      (node (ref "1") (pin "P") (pinfunction "P_P") (pintype "passive"))
    )
    (net (code "180") (name "unconnected-(1-PadS)") (class "Default")
      (node (ref "1") (pin "S") (pinfunction "S_S") (pintype "passive"))
    )
    (net (code "181") (name "unconnected-(2,1MM_JACK-GNDBREAK-PadP$3)") (class "Default")
      (node (ref "2,1MM_JACK") (pin "P$3") (pinfunction "GNDBREAK_P$3") (pintype "bidirectional"))
    )
    (net (code "182") (name "unconnected-(2-PadP)") (class "Default")
      (node (ref "2") (pin "P") (pinfunction "P_P") (pintype "passive"))
    )
    (net (code "183") (name "unconnected-(2-PadS)") (class "Default")
      (node (ref "2") (pin "S") (pinfunction "S_S") (pintype "passive"))
    )
    (net (code "184") (name "unconnected-(DS3231M-P$3_INT-Pad3)") (class "Default")
      (node (ref "DS3231M") (pin "3") (pinfunction "P$3_INT_3") (pintype "bidirectional"))
    )
    (net (code "185") (name "unconnected-(DS3231M-P$4_RST-Pad4)") (class "Default")
      (node (ref "DS3231M") (pin "4") (pinfunction "P$4_RST_4") (pintype "bidirectional"))
    )
    (net (code "186") (name "unconnected-(RESET-PadP)") (class "Default")
      (node (ref "RESET") (pin "P") (pinfunction "P_P") (pintype "passive"))
    )
    (net (code "187") (name "unconnected-(RESET-PadS)") (class "Default")
      (node (ref "RESET") (pin "S") (pinfunction "S_S") (pintype "passive"))
    )
    (net (code "188") (name "unconnected-(SHIFT_1-QH*-Pad9)") (class "Default")
      (node (ref "SHIFT_1") (pin "9") (pinfunction "QH*_9") (pintype "tri_state"))
    )
    (net (code "189") (name "unconnected-(U$1-CARD_DETECT-PadCARD_DETECT1)") (class "Default")
      (node (ref "U$1") (pin "CARD_DETECT1") (pinfunction "CARD_DETECT_CARD_DETECT1") (pintype "passive"))
    )
    (net (code "190") (name "unconnected-(U$1-CARD_DETECT1-PadCARD_DETECT2)") (class "Default")
      (node (ref "U$1") (pin "CARD_DETECT2") (pinfunction "CARD_DETECT1_CARD_DETECT2") (pintype "passive"))
    )
  )
)
